# Arduino_DUE_X_V02d-2Layer.net
KiCad netlist of a schematic drawn in Altium Designer
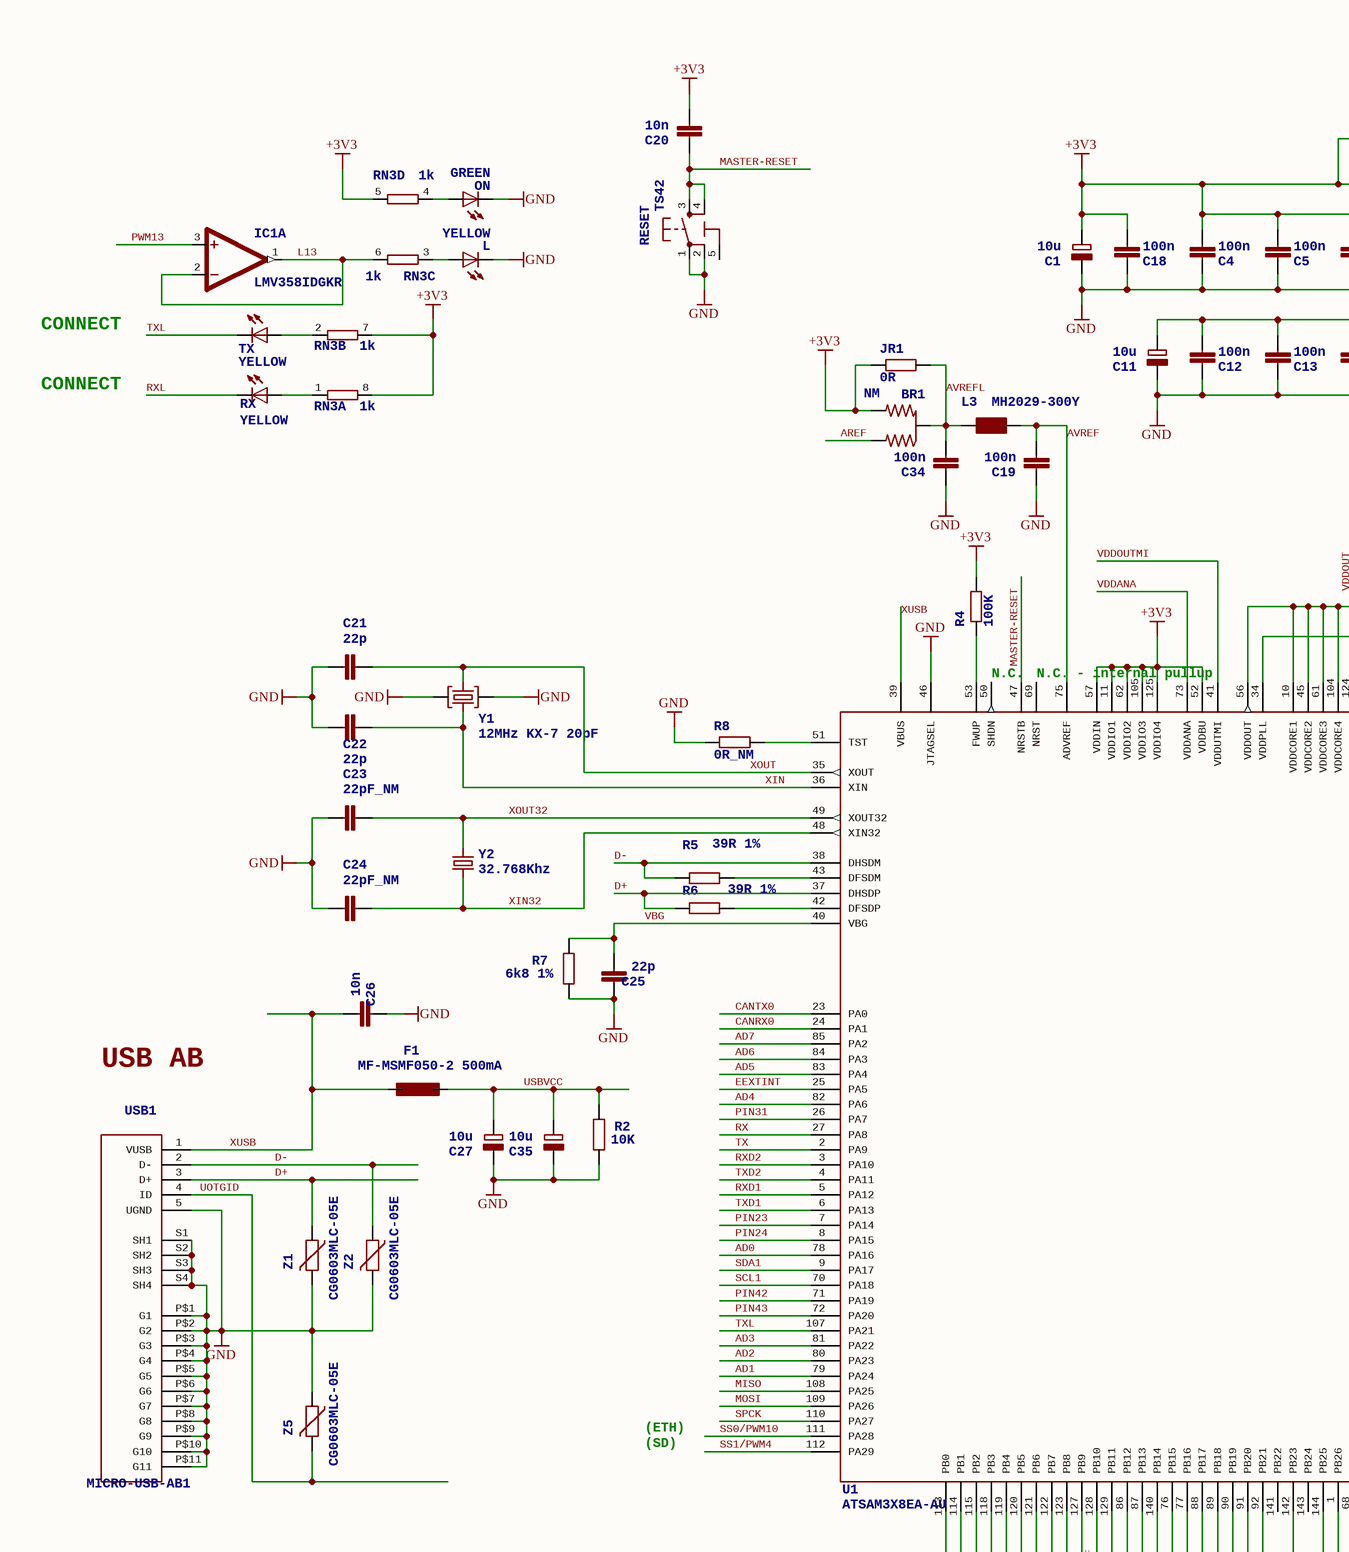
[diagram p0: Arduino_DUE_X_V02d-2Layer.SchDoc, top left]
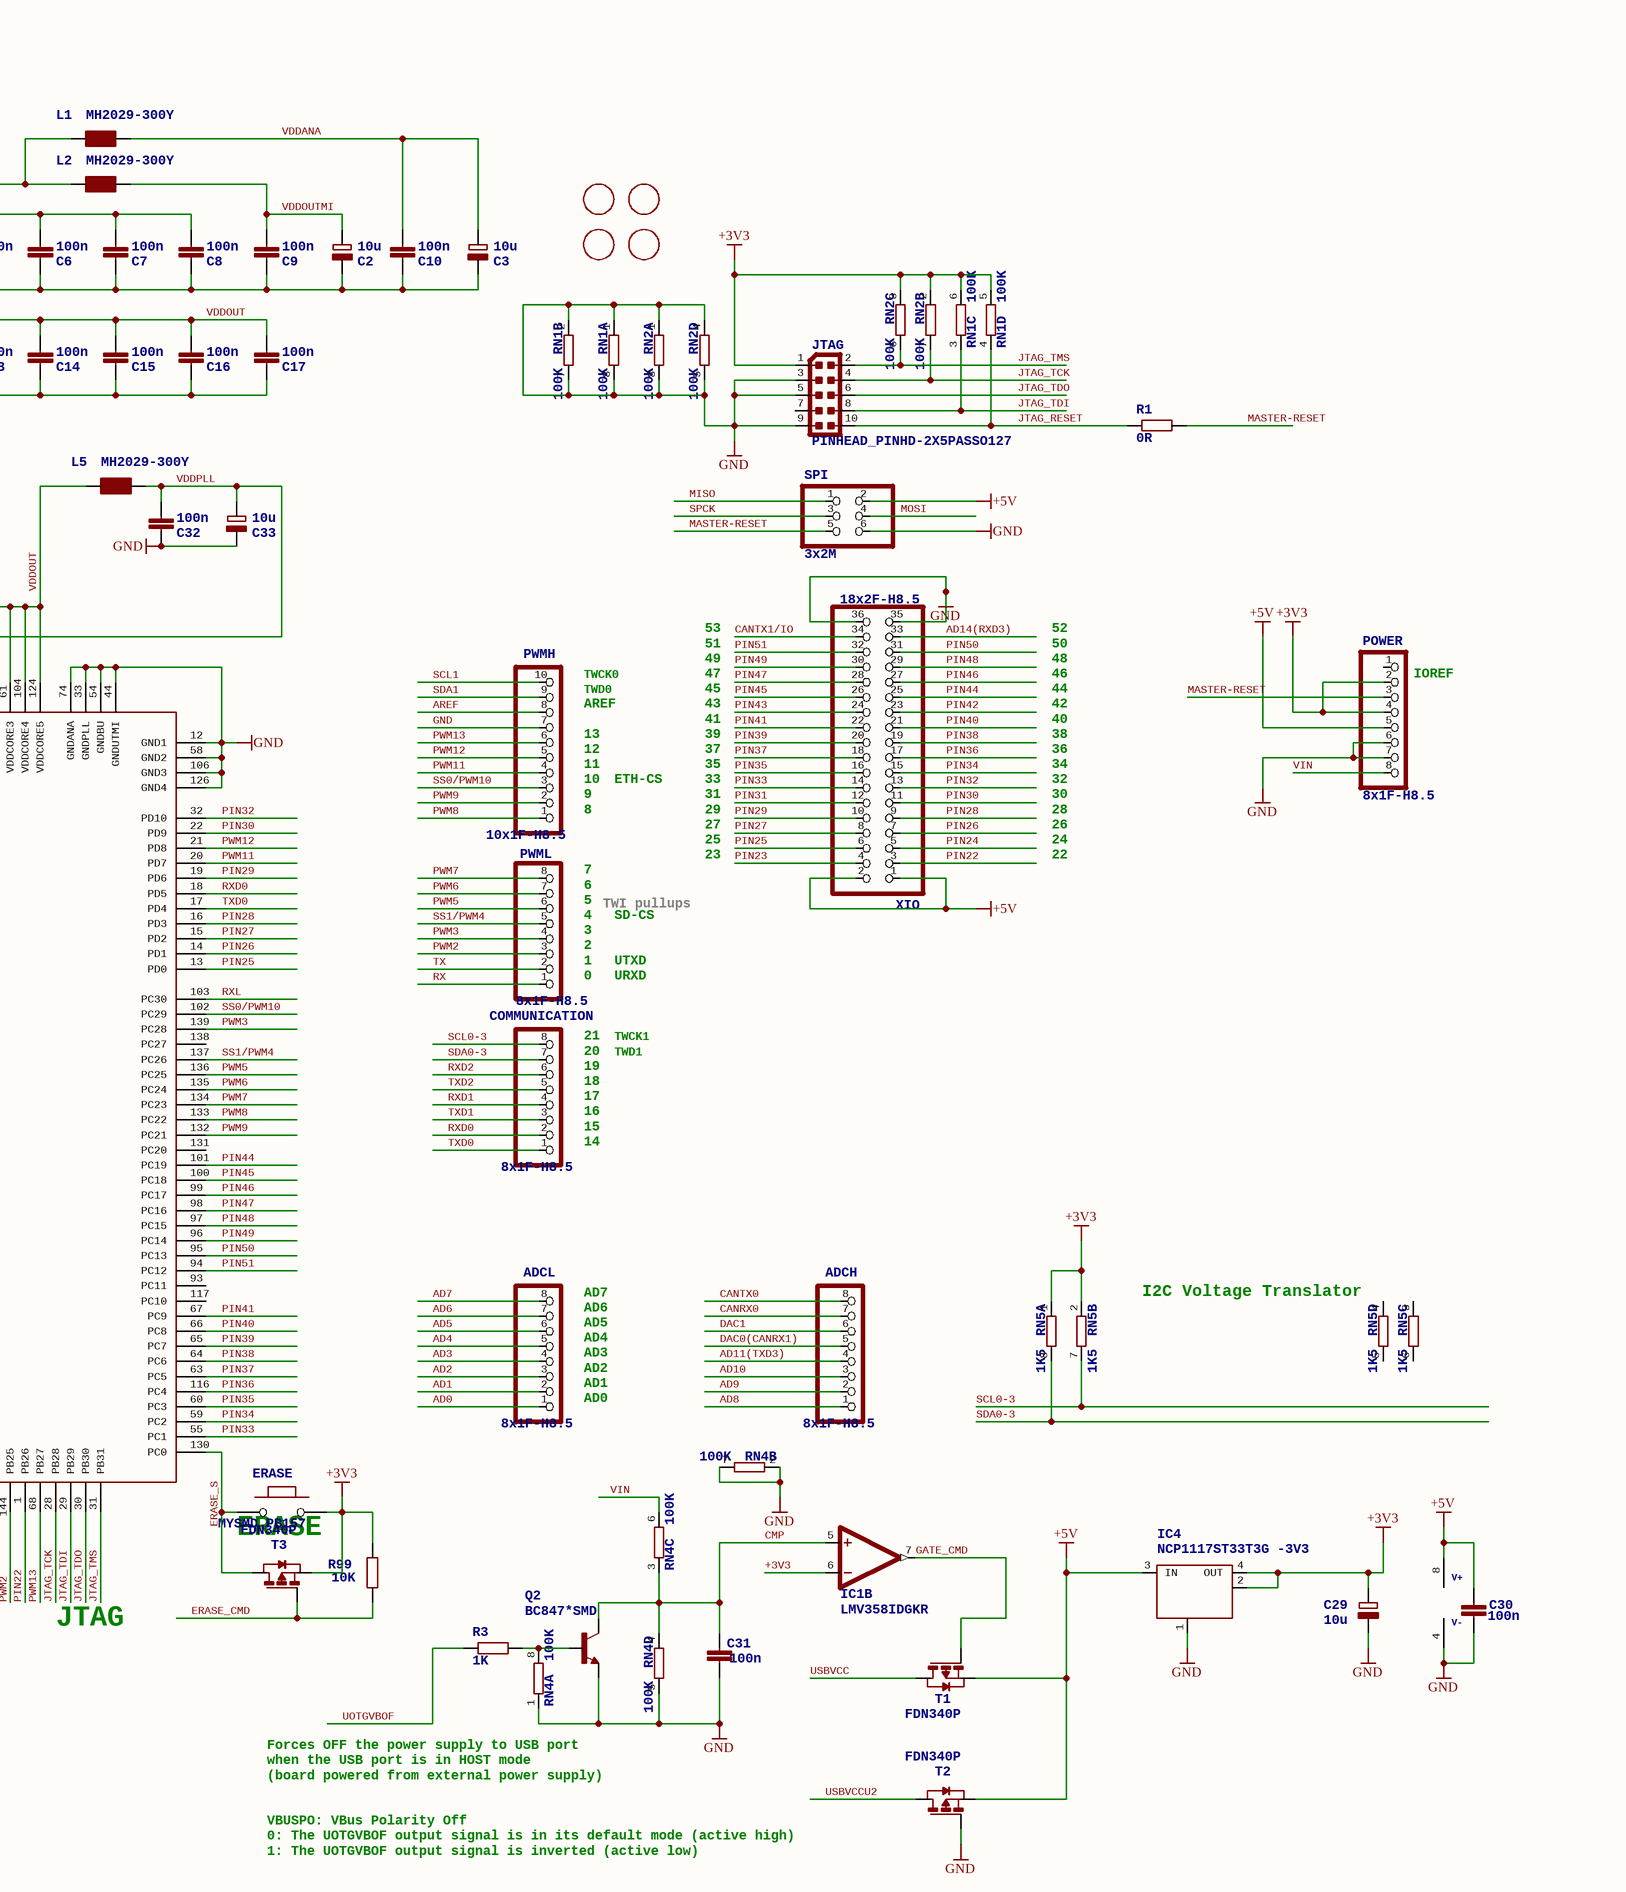
[diagram p1: Arduino_DUE_X_V02d-2Layer.SchDoc, top right]
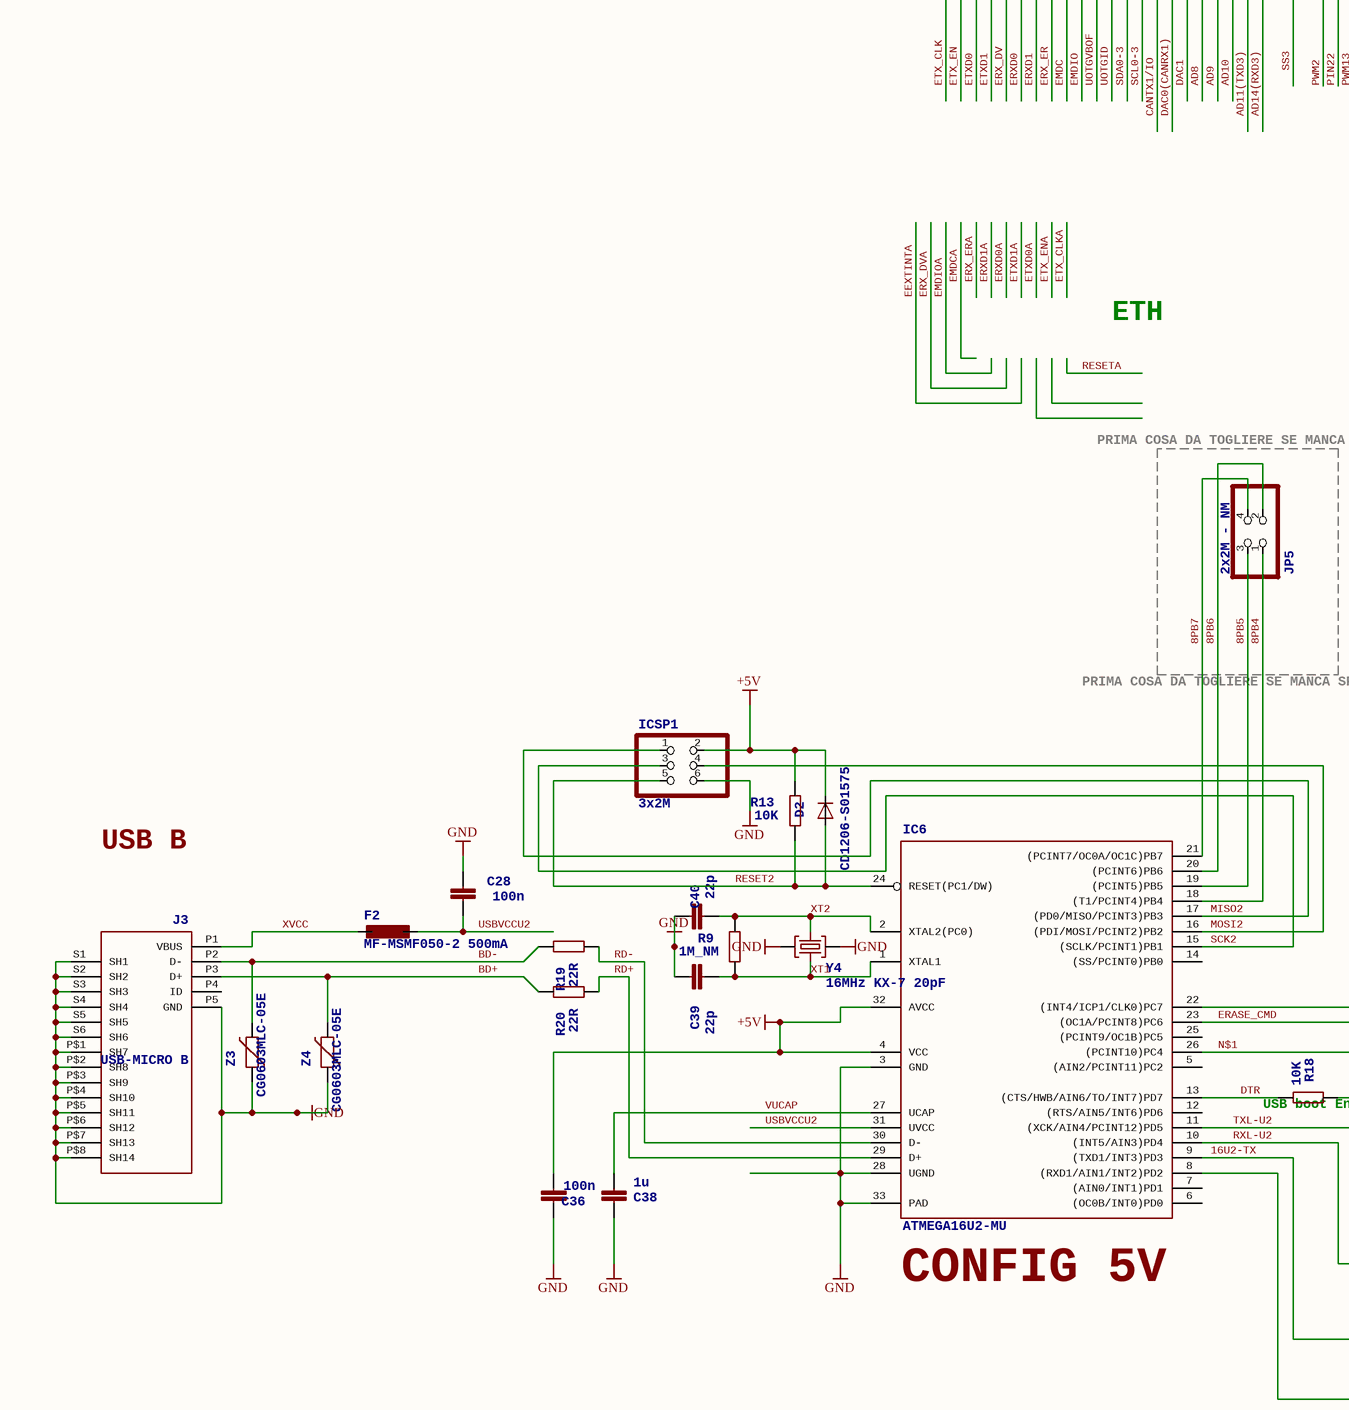
[diagram p2: Arduino_DUE_X_V02d-2Layer.SchDoc, bottom left]
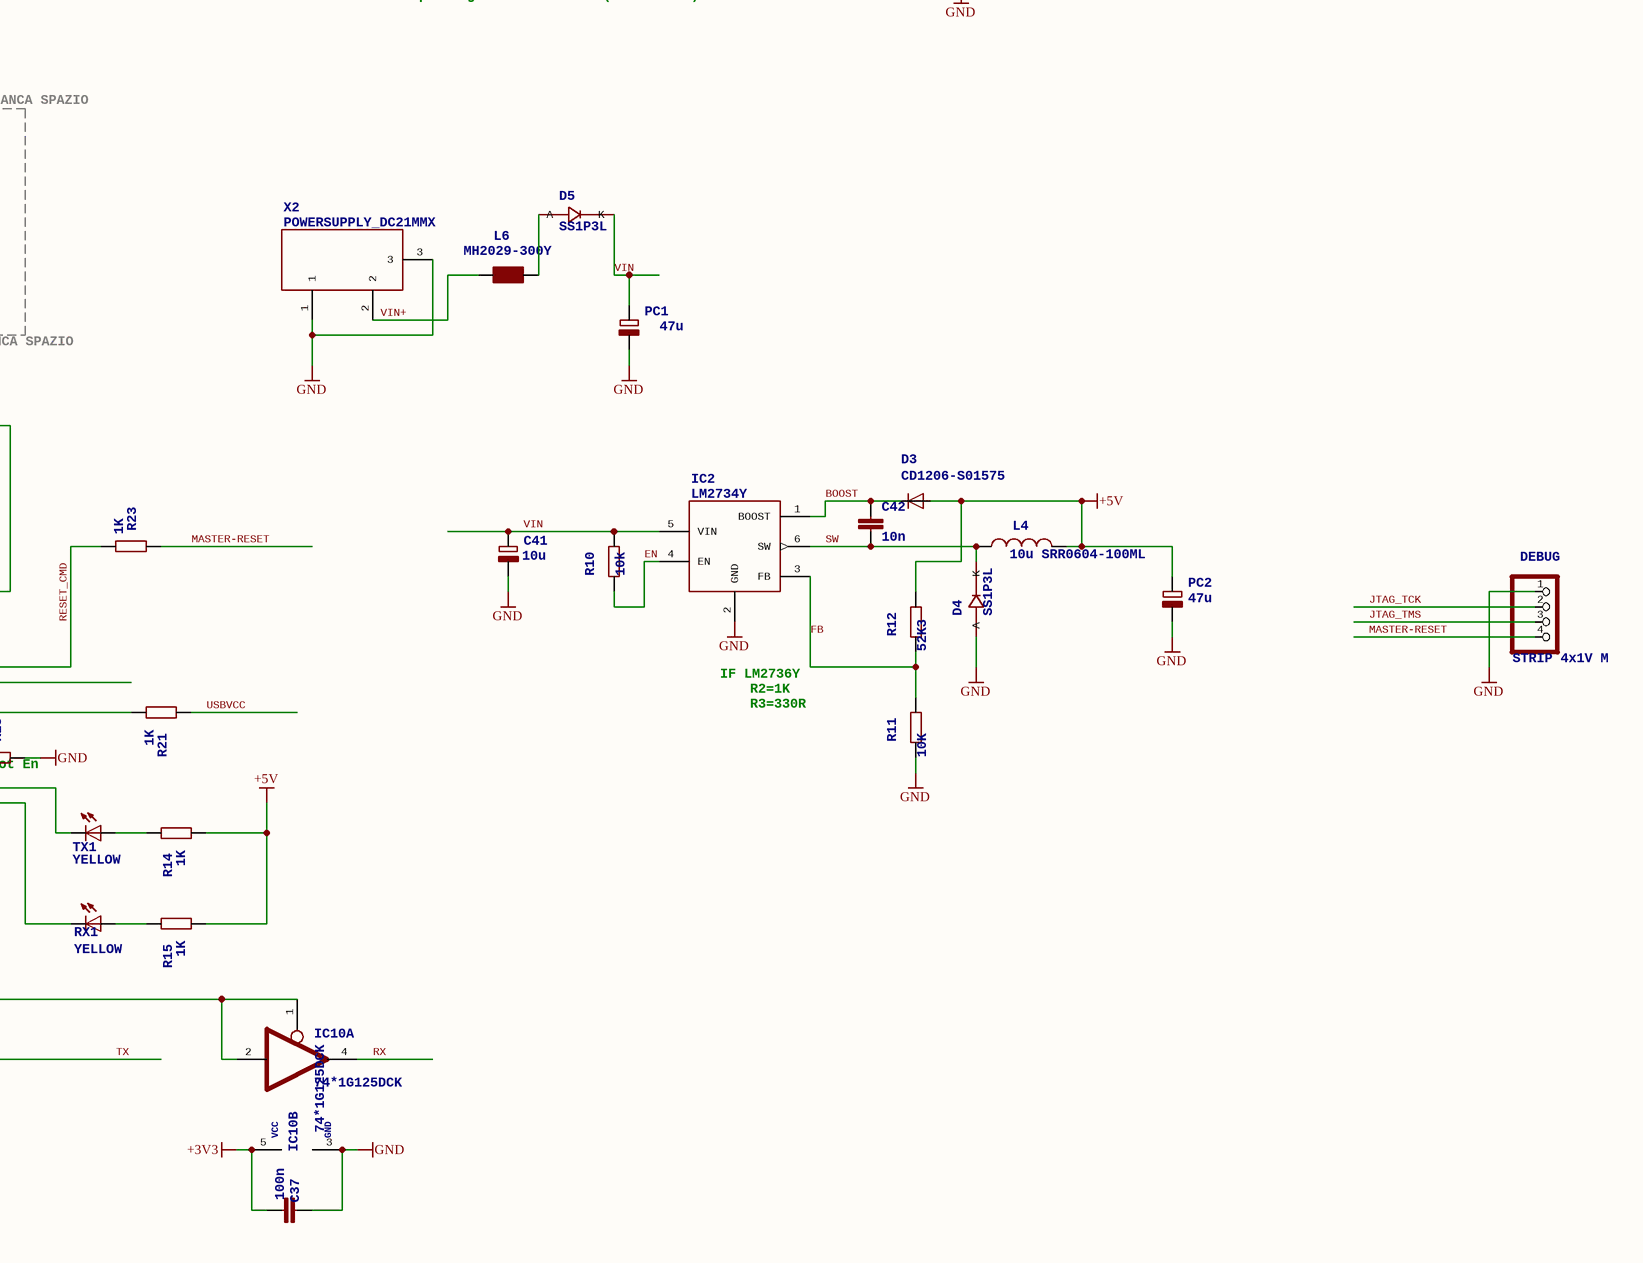
[diagram p3: Arduino_DUE_X_V02d-2Layer.SchDoc, bottom right]

(export (version "E")
  (design (tool "Eeschema 10.0.6"))
  (components
    (comp (ref "ADCH")
      (value "8x1F-H8.5")
      (footprint "1X08")
      (description "<b>PIN HEADER</b>")
      (libsource (lib "SmartPrj") (part "PINHD-1X8"))
    )
    (comp (ref "ADCL")
      (value "8x1F-H8.5")
      (footprint "1X08")
      (description "<b>PIN HEADER</b>")
      (libsource (lib "SmartPrj") (part "PINHD-1X8"))
    )
    (comp (ref "BR1")
      (value "NM")
      (footprint "J0402")
      (description "Three terminal jumper made from two 0402, 0603, 0805, etc.")
      (libsource (lib "bibaja") (part "J0402"))
    )
    (comp (ref "C1")
      (value "10u")
      (footprint "SMC_B")
      (description "<B>POLARIZED CAPACITOR</B>, European symbol")
      (libsource (lib "rcl") (part "CPOL-EUSMCB"))
    )
    (comp (ref "C2")
      (value "10u")
      (footprint "SMC_B")
      (description "<B>POLARIZED CAPACITOR</B>, European symbol")
      (libsource (lib "") (part "CPOL-EUSMCB_1"))
    )
    (comp (ref "C3")
      (value "10u")
      (footprint "SMC_B")
      (description "<B>POLARIZED CAPACITOR</B>, European symbol")
      (libsource (lib "") (part "CPOL-EUSMCB_1"))
    )
    (comp (ref "C4")
      (value "100n")
      (footprint "C0402")
      (description "<B>CAPACITOR</B>, European symbol")
      (libsource (lib "SmartPrj") (part "C-EUC0402"))
    )
    (comp (ref "C5")
      (value "100n")
      (footprint "C0402")
      (description "<B>CAPACITOR</B>, European symbol")
      (libsource (lib "SmartPrj") (part "C-EUC0402"))
    )
    (comp (ref "C6")
      (value "100n")
      (footprint "C0402")
      (description "<B>CAPACITOR</B>, European symbol")
      (libsource (lib "SmartPrj") (part "C-EUC0402"))
    )
    (comp (ref "C7")
      (value "100n")
      (footprint "C0402")
      (description "<B>CAPACITOR</B>, European symbol")
      (libsource (lib "SmartPrj") (part "C-EUC0402"))
    )
    (comp (ref "C8")
      (value "100n")
      (footprint "C0402")
      (description "<B>CAPACITOR</B>, European symbol")
      (libsource (lib "SmartPrj") (part "C-EUC0402"))
    )
    (comp (ref "C9")
      (value "100n")
      (footprint "C0402")
      (description "<B>CAPACITOR</B>, European symbol")
      (libsource (lib "SmartPrj") (part "C-EUC0402"))
    )
    (comp (ref "C10")
      (value "100n")
      (footprint "C0402")
      (description "<B>CAPACITOR</B>, European symbol")
      (libsource (lib "SmartPrj") (part "C-EUC0402"))
    )
    (comp (ref "C11")
      (value "10u")
      (footprint "SMC_B")
      (description "<B>POLARIZED CAPACITOR</B>, European symbol")
      (libsource (lib "rcl") (part "CPOL-EUSMCB"))
    )
    (comp (ref "C12")
      (value "100n")
      (footprint "C0402")
      (description "<B>CAPACITOR</B>, European symbol")
      (libsource (lib "SmartPrj") (part "C-EUC0402"))
    )
    (comp (ref "C13")
      (value "100n")
      (footprint "C0402")
      (description "<B>CAPACITOR</B>, European symbol")
      (libsource (lib "SmartPrj") (part "C-EUC0402"))
    )
    (comp (ref "C14")
      (value "100n")
      (footprint "C0402")
      (description "<B>CAPACITOR</B>, European symbol")
      (libsource (lib "SmartPrj") (part "C-EUC0402"))
    )
    (comp (ref "C15")
      (value "100n")
      (footprint "C0402")
      (description "<B>CAPACITOR</B>, European symbol")
      (libsource (lib "SmartPrj") (part "C-EUC0402"))
    )
    (comp (ref "C16")
      (value "100n")
      (footprint "C0402")
      (description "<B>CAPACITOR</B>, European symbol")
      (libsource (lib "SmartPrj") (part "C-EUC0402"))
    )
    (comp (ref "C17")
      (value "100n")
      (footprint "C0402")
      (description "<B>CAPACITOR</B>, European symbol")
      (libsource (lib "SmartPrj") (part "C-EUC0402"))
    )
    (comp (ref "C18")
      (value "100n")
      (footprint "C0402")
      (description "<B>CAPACITOR</B>, European symbol")
      (libsource (lib "SmartPrj") (part "C-EUC0402"))
    )
    (comp (ref "C19")
      (value "100n")
      (footprint "C0402")
      (description "<B>CAPACITOR</B>, European symbol")
      (libsource (lib "") (part "C-EUC0402_1"))
    )
    (comp (ref "C20")
      (value "10n")
      (footprint "C0402")
      (description "<B>CAPACITOR</B>, European symbol")
      (libsource (lib "") (part "C-EUC0402_1"))
    )
    (comp (ref "C21")
      (value "22p")
      (footprint "C0402")
      (description "<B>CAPACITOR</B>, European symbol")
      (libsource (lib "") (part "C-EUC0402_2"))
    )
    (comp (ref "C22")
      (value "22p")
      (footprint "C0402")
      (description "<B>CAPACITOR</B>, European symbol")
      (libsource (lib "") (part "C-EUC0402_2"))
    )
    (comp (ref "C23")
      (value "22pF_NM")
      (footprint "C0402")
      (description "<B>CAPACITOR</B>, European symbol")
      (libsource (lib "") (part "C-EUC0402_2"))
    )
    (comp (ref "C24")
      (value "22pF_NM")
      (footprint "C0402")
      (description "<B>CAPACITOR</B>, European symbol")
      (libsource (lib "") (part "C-EUC0402_2"))
    )
    (comp (ref "C25")
      (value "22p")
      (footprint "C0402")
      (description "<B>CAPACITOR</B>, European symbol")
      (libsource (lib "") (part "C-EUC0402_2"))
    )
    (comp (ref "C26")
      (value "10n")
      (footprint "C0402")
      (description "<B>CAPACITOR</B>, European symbol")
      (libsource (lib "SmartPrj") (part "C-EUC0402"))
    )
    (comp (ref "C27")
      (value "10u")
      (footprint "SMC_B")
      (description "<B>POLARIZED CAPACITOR</B>, European symbol")
      (libsource (lib "rcl") (part "CPOL-EUSMCB"))
    )
    (comp (ref "C28")
      (value "100n")
      (footprint "C0402")
      (description "<B>CAPACITOR</B>, European symbol")
      (libsource (lib "") (part "C-EUC0402_1"))
    )
    (comp (ref "C29")
      (value "10u")
      (footprint "SMC_B")
      (description "<B>POLARIZED CAPACITOR</B>, European symbol")
      (libsource (lib "rcl") (part "CPOL-EUSMCB"))
    )
    (comp (ref "C30")
      (value "100n")
      (footprint "C0402")
      (description "<B>CAPACITOR</B>, European symbol")
      (libsource (lib "SmartPrj") (part "C-EUC0402"))
    )
    (comp (ref "C31")
      (value "100n")
      (footprint "C0402")
      (description "<B>CAPACITOR</B>, European symbol")
      (libsource (lib "SmartPrj") (part "C-EUC0402"))
    )
    (comp (ref "C32")
      (value "100n")
      (footprint "C0402")
      (description "<B>CAPACITOR</B>, European symbol")
      (libsource (lib "SmartPrj") (part "C-EUC0402"))
    )
    (comp (ref "C33")
      (value "10u")
      (footprint "SMC_B")
      (description "<B>POLARIZED CAPACITOR</B>, European symbol")
      (libsource (lib "") (part "CPOL-EUSMCB_1"))
    )
    (comp (ref "C34")
      (value "100n")
      (footprint "C0402")
      (description "<B>CAPACITOR</B>, European symbol")
      (libsource (lib "") (part "C-EUC0402_1"))
    )
    (comp (ref "C35")
      (value "10u")
      (footprint "SMC_B")
      (description "<B>POLARIZED CAPACITOR</B>, European symbol")
      (libsource (lib "rcl") (part "CPOL-EUSMCB"))
    )
    (comp (ref "C36")
      (value "100n")
      (footprint "C0402")
      (description "<B>CAPACITOR</B>, European symbol")
      (libsource (lib "") (part "C-EUC0402_2"))
    )
    (comp (ref "C37")
      (value "100n")
      (footprint "C0402")
      (description "<B>CAPACITOR</B>, European symbol")
      (libsource (lib "SmartPrj") (part "C-EUC0402"))
    )
    (comp (ref "C38")
      (value "1u")
      (footprint "C0402")
      (description "<B>CAPACITOR</B>, European symbol")
      (libsource (lib "") (part "C-EUC0402_2"))
    )
    (comp (ref "C39")
      (value "22p")
      (footprint "C0402")
      (description "<B>CAPACITOR</B>, European symbol")
      (libsource (lib "") (part "C-EUC0402_2"))
    )
    (comp (ref "C40")
      (value "22p")
      (footprint "C0402")
      (description "<B>CAPACITOR</B>, European symbol")
      (libsource (lib "") (part "C-EUC0402_2"))
    )
    (comp (ref "C41")
      (value "10u")
      (footprint "SMC_B")
      (description "<B>POLARIZED CAPACITOR</B>, European symbol")
      (libsource (lib "rcl") (part "CPOL-EUSMCB"))
    )
    (comp (ref "C42")
      (value "10n")
      (footprint "C0603-ROUND")
      (description "<B>CAPACITOR</B>, European symbol")
      (libsource (lib "SmartPrj") (part "C-EUC0603"))
    )
    (comp (ref "COMMUNICATION")
      (value "8x1F-H8.5")
      (footprint "1X08")
      (description "<b>PIN HEADER</b>")
      (libsource (lib "SmartPrj") (part "PINHD-1X8"))
    )
    (comp (ref "D2")
      (value "CD1206-S01575")
      (footprint "MINIMELF")
      (description "<b>DIODE</b>")
      (libsource (lib "diode") (part "DIODE-MINIMELF"))
    )
    (comp (ref "D3")
      (value "CD1206-S01575")
      (footprint "MINIMELF")
      (description "<b>DIODE</b>")
      (libsource (lib "diode") (part "DIODE-MINIMELF"))
    )
    (comp (ref "D4") (value "SS1P3L") (footprint "DO220AAL") (libsource (lib "SmartPrj") (part "SS1P3L")))
    (comp (ref "D5") (value "SS1P3L") (footprint "DO220AAL") (libsource (lib "SmartPrj") (part "SS1P3L")))
    (comp (ref "DEBUG")
      (value "STRIP 4x1V M")
      (footprint "1X04")
      (description "<b>PIN HEADER</b>")
      (libsource (lib "pinhead") (part "PINHD-1X4"))
    )
    (comp (ref "ERASE")
      (value "MYSMD_PB157")
      (footprint "SMD_157SW")
      (libsource (lib "SmartPrj") (part "MYSMD_PB157"))
    )
    (comp (ref "F1")
      (value "MF-MSMF050-2 500mA")
      (footprint "L1812")
      (description "<B>INDUCTOR</B>, European symbol")
      (libsource (lib "rcl") (part "L-EUL1812"))
    )
    (comp (ref "F2")
      (value "MF-MSMF050-2 500mA")
      (footprint "L1812")
      (description "<B>INDUCTOR</B>, European symbol")
      (libsource (lib "rcl") (part "L-EUL1812"))
    )
    (comp (ref "FID1")
      (value "FIDUCIALMOUNT")
      (footprint "FIDUCIA-MOUNT")
      (libsource (lib "SmartPrj") (part "FIDUCIALMOUNT"))
    )
    (comp (ref "FID2")
      (value "FIDUCIALMOUNT")
      (footprint "FIDUCIA-MOUNT")
      (libsource (lib "SmartPrj") (part "FIDUCIALMOUNT"))
    )
    (comp (ref "FID3")
      (value "FIDUCIALMOUNT")
      (footprint "FIDUCIA-MOUNT")
      (libsource (lib "SmartPrj") (part "FIDUCIALMOUNT"))
    )
    (comp (ref "FID4")
      (value "FIDUCIALMOUNT")
      (footprint "FIDUCIA-MOUNT")
      (libsource (lib "SmartPrj") (part "FIDUCIALMOUNT"))
    )
    (comp (ref "IC1")
      (value "LMV358IDGKR")
      (footprint "MSOP08")
      (fields (field (name "V+") "V+") (field (name "V-") "V-"))
      (libsource (lib "linear") (part "LMV358?*MM"))
    )
    (comp (ref "IC2") (value "LM2734Y") (footprint "SOT23-6") (libsource (lib "SmartPrj") (part "LM2736Y")))
    (comp (ref "IC4")
      (value "NCP1117ST33T3G -3V3")
      (footprint "SOT223")
      (libsource (lib "linear") (part "MC33269ST*"))
    )
    (comp (ref "IC6")
      (value "ATMEGA16U2-MU")
      (footprint "MLF32")
      (libsource (lib "SmartPrj") (part "ATMEGA16U2-MU"))
    )
    (comp (ref "IC10")
      (value "74*1G125DCK")
      (footprint "SC70-5")
      (description "Single Bus <b>Buffer </b>Gate with 3-State Output")
      (fields (field (name "GND") "GND") (field (name "VCC") "VCC"))
      (libsource (lib "74xx-little-us") (part "74*1G125DCK"))
    )
    (comp (ref "ICSP1")
      (value "3x2M")
      (footprint "2X03")
      (description "<b>PIN HEADER</b>")
      (libsource (lib "SmartPrj") (part "PINHD-2X3"))
    )
    (comp (ref "J3")
      (value "USB-MICRO B")
      (footprint "CON2_USB_MICRO_B_AT")
      (libsource (lib "SmartPrj") (part "MYCON2_USB-MINI-B"))
    )
    (comp (ref "JP5")
      (value "2x2M - NM")
      (footprint "2X02")
      (description "<b>PIN HEADER</b>")
      (libsource (lib "SmartPrj") (part "PINHD-2X2"))
    )
    (comp (ref "JR1")
      (value "0R")
      (footprint "R0402")
      (description "<B>RESISTOR</B>, European symbol")
      (libsource (lib "SmartPrj") (part "R-EU_R0402"))
    )
    (comp (ref "JTAG")
      (value "PINHEAD_PINHD-2X5PASSO127")
      (footprint "PINHEAD_2X05_127")
      (description "<b>PIN HEADER</b>")
      (libsource (lib "Arduino_Wifi_shield_v018_tG") (part "PINHEAD_PINHD-2X5PASSO127"))
    )
    (comp (ref "L")
      (value "YELLOW")
      (footprint "CHIP-LED0805")
      (libsource (lib "led") (part "LEDCHIP-LED0805"))
    )
    (comp (ref "L1")
      (value "MH2029-300Y")
      (footprint "0805")
      (libsource (lib "wuerth-elektronik") (part "WE-CBF_0805"))
    )
    (comp (ref "L2")
      (value "MH2029-300Y")
      (footprint "0805")
      (libsource (lib "wuerth-elektronik") (part "WE-CBF_0805"))
    )
    (comp (ref "L3")
      (value "MH2029-300Y")
      (footprint "0805")
      (libsource (lib "wuerth-elektronik") (part "WE-CBF_0805"))
    )
    (comp (ref "L4")
      (value "10u SRR0604-100ML")
      (footprint "SRR0604")
      (description "<B>INDUCTOR</B>, American symbol")
      (libsource (lib "SmartPrj") (part "L-USSRR0604"))
    )
    (comp (ref "L5")
      (value "MH2029-300Y")
      (footprint "0805")
      (libsource (lib "wuerth-elektronik") (part "WE-CBF_0805"))
    )
    (comp (ref "L6") (value "MH2029-300Y") (footprint "0805") (libsource (lib "") (part "WE-CBF_0805_1")))
    (comp (ref "ON")
      (value "GREEN")
      (footprint "CHIP-LED0805")
      (libsource (lib "led") (part "LEDCHIP-LED0805"))
    )
    (comp (ref "PC1")
      (value "47u")
      (footprint "PANASONIC_D")
      (description "<B>POLARIZED CAPACITOR</B>, European symbol")
      (libsource (lib "rcl") (part "CPOL-EUD"))
    )
    (comp (ref "PC2")
      (value "47u")
      (footprint "PANASONIC_D")
      (description "<B>POLARIZED CAPACITOR</B>, European symbol")
      (libsource (lib "rcl") (part "CPOL-EUD"))
    )
    (comp (ref "POWER")
      (value "8x1F-H8.5")
      (footprint "1X08")
      (description "<b>PIN HEADER</b>")
      (libsource (lib "SmartPrj") (part "PINHD-1X8"))
    )
    (comp (ref "PWMH")
      (value "10x1F-H8.5")
      (footprint "1X10")
      (description "<b>PIN HEADER</b>")
      (libsource (lib "SmartPrj") (part "PINHD-1X10"))
    )
    (comp (ref "PWML")
      (value "8x1F-H8.5")
      (footprint "1X08")
      (description "<b>PIN HEADER</b>")
      (libsource (lib "SmartPrj") (part "PINHD-1X8"))
    )
    (comp (ref "Q2")
      (value "BC847*SMD")
      (footprint "SOT23")
      (description "NPN Transistor")
      (libsource (lib "transistor-npn") (part "BC847*SMD"))
    )
    (comp (ref "R1")
      (value "0R")
      (footprint "R0402")
      (description "<B>RESISTOR</B>, European symbol")
      (libsource (lib "SmartPrj") (part "R-EU_R0402"))
    )
    (comp (ref "R2")
      (value "10K")
      (footprint "R0402")
      (description "<B>RESISTOR</B>, European symbol")
      (libsource (lib "SmartPrj") (part "R-EU_R0402"))
    )
    (comp (ref "R3")
      (value "1K")
      (footprint "R0402")
      (description "<B>RESISTOR</B>, European symbol")
      (libsource (lib "SmartPrj") (part "R-EU_R0402"))
    )
    (comp (ref "R4")
      (value "100K")
      (footprint "R0402")
      (description "<B>RESISTOR</B>, European symbol")
      (libsource (lib "SmartPrj") (part "R-EU_R0402"))
    )
    (comp (ref "R5")
      (value "39R 1%")
      (footprint "R0402")
      (description "<B>RESISTOR</B>, European symbol")
      (libsource (lib "SmartPrj") (part "R-EU_R0402"))
    )
    (comp (ref "R6")
      (value "39R 1%")
      (footprint "R0402")
      (description "<B>RESISTOR</B>, European symbol")
      (libsource (lib "SmartPrj") (part "R-EU_R0402"))
    )
    (comp (ref "R7")
      (value "6k8 1%")
      (footprint "R0603-ROUND")
      (description "<B>RESISTOR</B>, European symbol")
      (libsource (lib "SmartPrj") (part "R-EU_R0603"))
    )
    (comp (ref "R8")
      (value "0R_NM")
      (footprint "R0402")
      (description "<B>RESISTOR</B>, European symbol")
      (libsource (lib "SmartPrj") (part "R-EU_R0402"))
    )
    (comp (ref "R9")
      (value "1M_NM")
      (footprint "R0402")
      (description "<B>RESISTOR</B>, European symbol")
      (libsource (lib "SmartPrj") (part "R-EU_R0402"))
    )
    (comp (ref "R10")
      (value "10k")
      (footprint "R0402")
      (description "<B>RESISTOR</B>, European symbol")
      (libsource (lib "SmartPrj") (part "R-EU_R0402"))
    )
    (comp (ref "R11")
      (value "10K")
      (footprint "R0603-ROUND")
      (description "<B>RESISTOR</B>, European symbol")
      (libsource (lib "SmartPrj") (part "R-EU_0603-RND"))
    )
    (comp (ref "R12")
      (value "52K3")
      (footprint "R0603-ROUND")
      (description "<B>RESISTOR</B>, European symbol")
      (libsource (lib "SmartPrj") (part "R-EU_0603-RND"))
    )
    (comp (ref "R13")
      (value "10K")
      (footprint "R0402")
      (description "<B>RESISTOR</B>, European symbol")
      (libsource (lib "SmartPrj") (part "R-EU_R0402"))
    )
    (comp (ref "R14")
      (value "1K")
      (footprint "R0402")
      (description "<B>RESISTOR</B>, European symbol")
      (libsource (lib "SmartPrj") (part "R-EU_R0402"))
    )
    (comp (ref "R15")
      (value "1K")
      (footprint "R0402")
      (description "<B>RESISTOR</B>, European symbol")
      (libsource (lib "SmartPrj") (part "R-EU_R0402"))
    )
    (comp (ref "R18")
      (value "10K")
      (footprint "R0402")
      (description "<B>RESISTOR</B>, European symbol")
      (libsource (lib "SmartPrj") (part "R-EU_R0402"))
    )
    (comp (ref "R19")
      (value "22R")
      (footprint "R0402")
      (description "<B>RESISTOR</B>, European symbol")
      (libsource (lib "SmartPrj") (part "R-EU_R0402"))
    )
    (comp (ref "R20")
      (value "22R")
      (footprint "R0402")
      (description "<B>RESISTOR</B>, European symbol")
      (libsource (lib "SmartPrj") (part "R-EU_R0402"))
    )
    (comp (ref "R21")
      (value "1K")
      (footprint "R0402")
      (description "<B>RESISTOR</B>, European symbol")
      (libsource (lib "SmartPrj") (part "R-EU_R0402"))
    )
    (comp (ref "R23")
      (value "1K")
      (footprint "R0402")
      (description "<B>RESISTOR</B>, European symbol")
      (libsource (lib "SmartPrj") (part "R-EU_R0402"))
    )
    (comp (ref "R99")
      (value "10K")
      (footprint "R0402")
      (description "<B>RESISTOR</B>, European symbol")
      (libsource (lib "SmartPrj") (part "R-EU_R0402"))
    )
    (comp (ref "RESET")
      (value "TS42")
      (footprint "TS42")
      (description "TS42\n\nDongnan Electronics\n\nTact switch\n\nVDC 12V - 50mA")
      (libsource (lib "SmartPrj") (part "TS42"))
    )
    (comp (ref "RN1")
      (value "100K")
      (footprint "CAT16")
      (description "<b>Array Chip Resistor</b><p>\nSource: RS Component / Phycomp")
      (libsource (lib "resistor-dil") (part "4R-NCAT16"))
    )
    (comp (ref "RN2")
      (value "100K")
      (footprint "CAT16")
      (description "<b>Array Chip Resistor</b><p>\nSource: RS Component / Phycomp")
      (libsource (lib "resistor-dil") (part "4R-NCAT16"))
    )
    (comp (ref "RN3")
      (value "1k")
      (footprint "CAY16")
      (description "<b>Array Chip Resistor</b><p>\nSource: RS Component / Phycomp")
      (libsource (lib "resistor-dil") (part "4R-NCAY16"))
    )
    (comp (ref "RN4")
      (value "100K")
      (footprint "CAT16")
      (description "<b>Array Chip Resistor</b><p>\nSource: RS Component / Phycomp")
      (libsource (lib "resistor-dil") (part "4R-NCAT16"))
    )
    (comp (ref "RN5")
      (value "1K5")
      (footprint "CAT16")
      (description "<b>Array Chip Resistor</b><p>\nSource: RS Component / Phycomp")
      (libsource (lib "resistor-dil") (part "4R-NCAT16"))
    )
    (comp (ref "RX")
      (value "YELLOW")
      (footprint "CHIP-LED0805")
      (libsource (lib "led") (part "LEDCHIP-LED0805"))
    )
    (comp (ref "RX1")
      (value "YELLOW")
      (footprint "CHIP-LED0805")
      (libsource (lib "led") (part "LEDCHIP-LED0805"))
    )
    (comp (ref "SPI")
      (value "3x2M")
      (footprint "2X03")
      (description "<b>PIN HEADER</b>")
      (libsource (lib "SmartPrj") (part "PINHD-2X3"))
    )
    (comp (ref "T1")
      (value "FDN340P")
      (footprint "SOT-23")
      (description "<b>MOS FET</b>")
      (libsource (lib "") (part "PMOSSOT23_1"))
    )
    (comp (ref "T2")
      (value "FDN340P")
      (footprint "SOT-23")
      (description "<b>MOS FET</b>")
      (libsource (lib "zetex") (part "PMOSSOT23"))
    )
    (comp (ref "T3")
      (value "FDN340P")
      (footprint "SOT-23")
      (description "<b>MOS FET</b>")
      (libsource (lib "zetex") (part "PMOSSOT23"))
    )
    (comp (ref "TX")
      (value "YELLOW")
      (footprint "CHIP-LED0805")
      (libsource (lib "led") (part "LEDCHIP-LED0805"))
    )
    (comp (ref "TX1")
      (value "YELLOW")
      (footprint "CHIP-LED0805")
      (libsource (lib "led") (part "LEDCHIP-LED0805"))
    )
    (comp (ref "U1")
      (value "ATSAM3X8EA-AU")
      (footprint "LQFP144")
      (libsource (lib "SmartPrj") (part "ATSAM3X/AAU"))
    )
    (comp (ref "USB1")
      (value "MICRO-USB-AB1")
      (footprint "MCR-AB1-S-RA-SMT")
      (description "<B>Micro_USB ADAM-TECH</B> MCR-AB1-S-RA-SMT")
      (libsource (lib "SmartPrj") (part "MICRO_USB"))
    )
    (comp (ref "X2")
      (value "POWERSUPPLY_DC21MMX")
      (footprint "POWERSUPPLY_DC-21MM")
      (libsource (lib "SmartPrj") (part "POWERSUPPLY_DC21MMX"))
    )
    (comp (ref "XIO")
      (value "18x2F-H8.5")
      (footprint "2X18")
      (description "<b>PIN HEADER</b>")
      (libsource (lib "SmartPrj") (part "PINHD-2X18"))
    )
    (comp (ref "Y1")
      (value "12MHz KX-7 20pF")
      (footprint "CRYSTAL-3.2-2.5")
      (libsource (lib "SmartPrj") (part "CRYSTAL-3.2-2.5"))
    )
    (comp (ref "Y2")
      (value "32.768Khz")
      (footprint "RESONATOR_EPSON_FC_145")
      (libsource (lib "Arduino_Wifi_shield_v018_tG") (part "RESONATOR_EPSON_FC_145"))
    )
    (comp (ref "Y4")
      (value "16MHz KX-7 20pF")
      (footprint "CRYSTAL-3.2-2.5")
      (libsource (lib "SmartPrj") (part "CRYSTAL-3.2-2.5"))
    )
    (comp (ref "Z1")
      (value "CG0603MLC-05E")
      (footprint "CT/CN0603")
      (description "<b>VARISTOR</b>")
      (libsource (lib "varistor") (part "VARISTORCN0603"))
    )
    (comp (ref "Z2")
      (value "CG0603MLC-05E")
      (footprint "CT/CN0603")
      (description "<b>VARISTOR</b>")
      (libsource (lib "varistor") (part "VARISTORCN0603"))
    )
    (comp (ref "Z3")
      (value "CG0603MLC-05E")
      (footprint "CT/CN0603")
      (description "<b>VARISTOR</b>")
      (libsource (lib "varistor") (part "VARISTORCN0603"))
    )
    (comp (ref "Z4")
      (value "CG0603MLC-05E")
      (footprint "CT/CN0603")
      (description "<b>VARISTOR</b>")
      (libsource (lib "varistor") (part "VARISTORCN0603"))
    )
    (comp (ref "Z5")
      (value "CG0603MLC-05E")
      (footprint "CT/CN0603")
      (description "<b>VARISTOR</b>")
      (libsource (lib "varistor") (part "VARISTORCN0603"))
    )
  )
  (nets
    (net (code "1") (name "+3V3") (class "Default")
      (node (ref "BR1") (pin "3") (pinfunction "2_3") (pintype "passive"))
      (node (ref "C1") (pin "+") (pinfunction "+_+") (pintype "passive"))
      (node (ref "C18") (pin "2") (pinfunction "2_2") (pintype "passive"))
      (node (ref "C20") (pin "2") (pinfunction "2_2") (pintype "passive"))
      (node (ref "C29") (pin "+") (pinfunction "+_+") (pintype "passive"))
      (node (ref "C37") (pin "1") (pinfunction "1_1") (pintype "passive"))
      (node (ref "C4") (pin "2") (pinfunction "2_2") (pintype "passive"))
      (node (ref "C5") (pin "2") (pinfunction "2_2") (pintype "passive"))
      (node (ref "C6") (pin "2") (pinfunction "2_2") (pintype "passive"))
      (node (ref "C7") (pin "2") (pinfunction "2_2") (pintype "passive"))
      (node (ref "C8") (pin "2") (pinfunction "2_2") (pintype "passive"))
      (node (ref "ERASE") (pin "1") (pinfunction "1_1") (pintype "passive"))
      (node (ref "IC1") (pin "6") (pinfunction "-IN_6") (pintype "passive"))
      (node (ref "IC10") (pin "5") (pinfunction "VCC_5") (pintype "power_in"))
      (node (ref "IC4") (pin "2") (pinfunction "OUT_2") (pintype "passive"))
      (node (ref "IC4") (pin "4") (pinfunction "OUT_4") (pintype "passive"))
      (node (ref "JR1") (pin "1") (pinfunction "1_1") (pintype "passive"))
      (node (ref "JTAG") (pin "1") (pinfunction "1_1") (pintype "passive"))
      (node (ref "L1") (pin "1") (pinfunction "1_1") (pintype "passive"))
      (node (ref "L2") (pin "1") (pinfunction "1_1") (pintype "passive"))
      (node (ref "POWER") (pin "2") (pinfunction "2_2") (pintype "passive"))
      (node (ref "POWER") (pin "4") (pinfunction "4_4") (pintype "passive"))
      (node (ref "R4") (pin "2") (pinfunction "2_2") (pintype "passive"))
      (node (ref "R99") (pin "2") (pinfunction "2_2") (pintype "passive"))
      (node (ref "RN1") (pin "5") (pinfunction "2_5") (pintype "passive"))
      (node (ref "RN1") (pin "6") (pinfunction "2_6") (pintype "passive"))
      (node (ref "RN2") (pin "2") (pinfunction "1_2") (pintype "passive"))
      (node (ref "RN2") (pin "3") (pinfunction "1_3") (pintype "passive"))
      (node (ref "RN3") (pin "5") (pinfunction "2_5") (pintype "passive"))
      (node (ref "RN3") (pin "7") (pinfunction "2_7") (pintype "passive"))
      (node (ref "RN3") (pin "8") (pinfunction "2_8") (pintype "passive"))
      (node (ref "RN5") (pin "1") (pinfunction "1_1") (pintype "passive"))
      (node (ref "RN5") (pin "2") (pinfunction "1_2") (pintype "passive"))
      (node (ref "T3") (pin "2") (pinfunction "S_2") (pintype "passive"))
      (node (ref "U1") (pin "105") (pinfunction "VDDIO3_105") (pintype "power_in"))
      (node (ref "U1") (pin "11") (pinfunction "VDDIO1_11") (pintype "power_in"))
      (node (ref "U1") (pin "125") (pinfunction "VDDIO4_125") (pintype "power_in"))
      (node (ref "U1") (pin "52") (pinfunction "VDDBU_52") (pintype "power_in"))
      (node (ref "U1") (pin "57") (pinfunction "VDDIN_57") (pintype "power_in"))
      (node (ref "U1") (pin "62") (pinfunction "VDDIO2_62") (pintype "power_in"))
    )
    (net (code "2") (name "+5V") (class "Default")
      (node (ref "C30") (pin "2") (pinfunction "2_2") (pintype "passive"))
      (node (ref "C36") (pin "1") (pinfunction "1_1") (pintype "passive"))
      (node (ref "D2") (pin "C") (pinfunction "C_C") (pintype "passive"))
      (node (ref "D3") (pin "A") (pinfunction "A_A") (pintype "passive"))
      (node (ref "IC1") (pin "8") (pinfunction "V+_8") (pintype "power_in"))
      (node (ref "IC4") (pin "3") (pinfunction "IN_3") (pintype "passive"))
      (node (ref "IC6") (pin "32") (pinfunction "AVCC_32") (pintype "power_in"))
      (node (ref "IC6") (pin "4") (pinfunction "VCC_4") (pintype "power_in"))
      (node (ref "ICSP1") (pin "2") (pinfunction "2_2") (pintype "passive"))
      (node (ref "L4") (pin "P$2") (pinfunction "2_P$2") (pintype "passive"))
      (node (ref "PC2") (pin "+") (pinfunction "+_+") (pintype "passive"))
      (node (ref "POWER") (pin "5") (pinfunction "5_5") (pintype "passive"))
      (node (ref "R12") (pin "1") (pinfunction "1_1") (pintype "passive"))
      (node (ref "R13") (pin "2") (pinfunction "2_2") (pintype "passive"))
      (node (ref "R14") (pin "1") (pinfunction "1_1") (pintype "passive"))
      (node (ref "R15") (pin "1") (pinfunction "1_1") (pintype "passive"))
      (node (ref "SPI") (pin "2") (pinfunction "2_2") (pintype "passive"))
      (node (ref "T1") (pin "2") (pinfunction "S_2") (pintype "passive"))
      (node (ref "T2") (pin "2") (pinfunction "S_2") (pintype "passive"))
      (node (ref "XIO") (pin "1") (pinfunction "1_1") (pintype "passive"))
      (node (ref "XIO") (pin "2") (pinfunction "2_2") (pintype "passive"))
    )
    (net (code "3") (name "/8PB4") (class "Default")
      (node (ref "IC6") (pin "18") (pinfunction "(T1/PCINT4)PB4_18") (pintype "passive"))
      (node (ref "JP5") (pin "1") (pinfunction "1_1") (pintype "passive"))
    )
    (net (code "4") (name "/8PB5") (class "Default")
      (node (ref "IC6") (pin "19") (pinfunction "(PCINT5)PB5_19") (pintype "passive"))
      (node (ref "JP5") (pin "3") (pinfunction "3_3") (pintype "passive"))
    )
    (net (code "5") (name "/8PB6") (class "Default")
      (node (ref "IC6") (pin "20") (pinfunction "(PCINT6)PB6_20") (pintype "passive"))
      (node (ref "JP5") (pin "2") (pinfunction "2_2") (pintype "passive"))
    )
    (net (code "6") (name "/8PB7") (class "Default")
      (node (ref "IC6") (pin "21") (pinfunction "(PCINT7/OC0A/OC1C)PB7_21") (pintype "passive"))
      (node (ref "JP5") (pin "4") (pinfunction "4_4") (pintype "passive"))
    )
    (net (code "7") (name "/16U2-TX") (class "Default")
      (node (ref "IC10") (pin "1") (pinfunction "OE_1") (pintype "passive"))
      (node (ref "IC10") (pin "2") (pinfunction "I_2") (pintype "passive"))
      (node (ref "IC6") (pin "9") (pinfunction "(TXD1/INT3)PD3_9") (pintype "passive"))
    )
    (net (code "8") (name "/AD0") (class "Default")
      (node (ref "ADCL") (pin "1") (pinfunction "1_1") (pintype "passive"))
      (node (ref "U1") (pin "78") (pinfunction "PA16_78") (pintype "passive"))
    )
    (net (code "9") (name "/AD1") (class "Default")
      (node (ref "ADCL") (pin "2") (pinfunction "2_2") (pintype "passive"))
      (node (ref "U1") (pin "79") (pinfunction "PA24_79") (pintype "passive"))
    )
    (net (code "10") (name "/AD2") (class "Default")
      (node (ref "ADCL") (pin "3") (pinfunction "3_3") (pintype "passive"))
      (node (ref "U1") (pin "80") (pinfunction "PA23_80") (pintype "passive"))
    )
    (net (code "11") (name "/AD3") (class "Default")
      (node (ref "ADCL") (pin "4") (pinfunction "4_4") (pintype "passive"))
      (node (ref "U1") (pin "81") (pinfunction "PA22_81") (pintype "passive"))
    )
    (net (code "12") (name "/AD4") (class "Default")
      (node (ref "ADCL") (pin "5") (pinfunction "5_5") (pintype "passive"))
      (node (ref "U1") (pin "82") (pinfunction "PA6_82") (pintype "passive"))
    )
    (net (code "13") (name "/AD5") (class "Default")
      (node (ref "ADCL") (pin "6") (pinfunction "6_6") (pintype "passive"))
      (node (ref "U1") (pin "83") (pinfunction "PA4_83") (pintype "passive"))
    )
    (net (code "14") (name "/AD6") (class "Default")
      (node (ref "ADCL") (pin "7") (pinfunction "7_7") (pintype "passive"))
      (node (ref "U1") (pin "84") (pinfunction "PA3_84") (pintype "passive"))
    )
    (net (code "15") (name "/AD7") (class "Default")
      (node (ref "ADCL") (pin "8") (pinfunction "8_8") (pintype "passive"))
      (node (ref "U1") (pin "85") (pinfunction "PA2_85") (pintype "passive"))
    )
    (net (code "16") (name "/AD8") (class "Default")
      (node (ref "ADCH") (pin "1") (pinfunction "1_1") (pintype "passive"))
      (node (ref "U1") (pin "88") (pinfunction "PB17_88") (pintype "passive"))
    )
    (net (code "17") (name "/AD9") (class "Default")
      (node (ref "ADCH") (pin "2") (pinfunction "2_2") (pintype "passive"))
      (node (ref "U1") (pin "89") (pinfunction "PB18_89") (pintype "passive"))
    )
    (net (code "18") (name "/AD10") (class "Default")
      (node (ref "ADCH") (pin "3") (pinfunction "3_3") (pintype "passive"))
      (node (ref "U1") (pin "90") (pinfunction "PB19_90") (pintype "passive"))
    )
    (net (code "19") (name "/AD11(TXD3)") (class "Default")
      (node (ref "ADCH") (pin "4") (pinfunction "4_4") (pintype "passive"))
      (node (ref "U1") (pin "91") (pinfunction "PB20_91") (pintype "passive"))
    )
    (net (code "20") (name "/AD14(RXD3)") (class "Default")
      (node (ref "U1") (pin "92") (pinfunction "PB21_92") (pintype "passive"))
      (node (ref "XIO") (pin "33") (pinfunction "33_33") (pintype "passive"))
    )
    (net (code "21") (name "/AREF") (class "Default")
      (node (ref "BR1") (pin "1") (pinfunction "1_1") (pintype "passive"))
      (node (ref "PWMH") (pin "8") (pinfunction "8_8") (pintype "passive"))
    )
    (net (code "22") (name "/AVREF") (class "Default")
      (node (ref "C19") (pin "2") (pinfunction "2_2") (pintype "passive"))
      (node (ref "L3") (pin "2") (pinfunction "2_2") (pintype "passive"))
      (node (ref "U1") (pin "75") (pinfunction "ADVREF_75") (pintype "power_in"))
    )
    (net (code "23") (name "/AVREFL") (class "Default")
      (node (ref "BR1") (pin "2") (pinfunction "C_2") (pintype "passive"))
      (node (ref "C34") (pin "2") (pinfunction "2_2") (pintype "passive"))
      (node (ref "JR1") (pin "2") (pinfunction "2_2") (pintype "passive"))
      (node (ref "L3") (pin "1") (pinfunction "1_1") (pintype "passive"))
    )
    (net (code "24") (name "/BD+") (class "Default")
      (node (ref "J3") (pin "P3") (pinfunction "D+_P3") (pintype "passive"))
      (node (ref "R20") (pin "2") (pinfunction "2_2") (pintype "passive"))
      (node (ref "Z4") (pin "2") (pinfunction "2_2") (pintype "passive"))
    )
    (net (code "25") (name "/BD-") (class "Default")
      (node (ref "J3") (pin "P2") (pinfunction "D-_P2") (pintype "passive"))
      (node (ref "R19") (pin "2") (pinfunction "2_2") (pintype "passive"))
      (node (ref "Z3") (pin "2") (pinfunction "2_2") (pintype "passive"))
    )
    (net (code "26") (name "/BOOST") (class "Default")
      (node (ref "C42") (pin "1") (pinfunction "1_1") (pintype "passive"))
      (node (ref "D3") (pin "C") (pinfunction "C_C") (pintype "passive"))
      (node (ref "IC2") (pin "1") (pinfunction "BOOST_1") (pintype "passive"))
    )
    (net (code "27") (name "/CANRX0") (class "Default")
      (node (ref "ADCH") (pin "7") (pinfunction "7_7") (pintype "passive"))
      (node (ref "U1") (pin "24") (pinfunction "PA1_24") (pintype "passive"))
    )
    (net (code "28") (name "/CANTX0") (class "Default")
      (node (ref "ADCH") (pin "8") (pinfunction "8_8") (pintype "passive"))
      (node (ref "U1") (pin "23") (pinfunction "PA0_23") (pintype "passive"))
    )
    (net (code "29") (name "/CANTX1{slash}IO") (class "Default")
      (node (ref "U1") (pin "140") (pinfunction "PB14_140") (pintype "passive"))
      (node (ref "XIO") (pin "34") (pinfunction "34_34") (pintype "passive"))
    )
    (net (code "30") (name "/CMP") (class "Default")
      (node (ref "C31") (pin "2") (pinfunction "2_2") (pintype "passive"))
      (node (ref "IC1") (pin "5") (pinfunction "+IN_5") (pintype "passive"))
      (node (ref "Q2") (pin "3") (pinfunction "C_3") (pintype "passive"))
      (node (ref "RN4") (pin "3") (pinfunction "1_3") (pintype "passive"))
      (node (ref "RN4") (pin "4") (pinfunction "1_4") (pintype "passive"))
    )
    (net (code "31") (name "/D+") (class "Default")
      (node (ref "R6") (pin "1") (pinfunction "1_1") (pintype "passive"))
      (node (ref "U1") (pin "37") (pinfunction "DHSDP_37") (pintype "passive"))
      (node (ref "USB1") (pin "3") (pinfunction "D+_3") (pintype "passive"))
      (node (ref "Z1") (pin "1") (pinfunction "1_1") (pintype "passive"))
    )
    (net (code "32") (name "/D-") (class "Default")
      (node (ref "R5") (pin "1") (pinfunction "1_1") (pintype "passive"))
      (node (ref "U1") (pin "38") (pinfunction "DHSDM_38") (pintype "passive"))
      (node (ref "USB1") (pin "2") (pinfunction "D-_2") (pintype "passive"))
      (node (ref "Z2") (pin "1") (pinfunction "1_1") (pintype "passive"))
    )
    (net (code "33") (name "/DAC0(CANRX1)") (class "Default")
      (node (ref "ADCH") (pin "5") (pinfunction "5_5") (pintype "passive"))
      (node (ref "U1") (pin "76") (pinfunction "PB15_76") (pintype "passive"))
    )
    (net (code "34") (name "/DAC1") (class "Default")
      (node (ref "ADCH") (pin "6") (pinfunction "6_6") (pintype "passive"))
      (node (ref "U1") (pin "77") (pinfunction "PB16_77") (pintype "passive"))
    )
    (net (code "35") (name "/DTR") (class "Default")
      (node (ref "IC6") (pin "13") (pinfunction "(CTS/HWB/AIN6/TO/INT7)PD7_13") (pintype "passive"))
      (node (ref "R18") (pin "1") (pinfunction "1_1") (pintype "passive"))
    )
    (net (code "36") (name "/EEXTINT") (class "Default")
      (node (ref "U1") (pin "25") (pinfunction "PA5_25") (pintype "passive"))
    )
    (net (code "38") (name "/EMDC") (class "Default")
      (node (ref "U1") (pin "123") (pinfunction "PB8_123") (pintype "passive"))
    )
    (net (code "40") (name "/EMDIO") (class "Default")
      (node (ref "U1") (pin "127") (pinfunction "PB9_127") (pintype "passive"))
    )
    (net (code "42") (name "/EN") (class "Default")
      (node (ref "IC2") (pin "4") (pinfunction "EN_4") (pintype "passive"))
      (node (ref "R10") (pin "2") (pinfunction "2_2") (pintype "passive"))
    )
    (net (code "43") (name "/ERASE_CMD") (class "Default")
      (node (ref "IC6") (pin "23") (pinfunction "(OC1A/PCINT8)PC6_23") (pintype "passive"))
      (node (ref "R99") (pin "1") (pinfunction "1_1") (pintype "passive"))
      (node (ref "T3") (pin "3") (pinfunction "G_3") (pintype "passive"))
    )
    (net (code "44") (name "/ERASE_S") (class "Default")
      (node (ref "ERASE") (pin "2") (pinfunction "2_2") (pintype "passive"))
      (node (ref "T3") (pin "1") (pinfunction "D_1") (pintype "passive"))
      (node (ref "U1") (pin "130") (pinfunction "PC0_130") (pintype "passive"))
    )
    (net (code "45") (name "/ERXD0") (class "Default")
      (node (ref "U1") (pin "120") (pinfunction "PB5_120") (pintype "passive"))
    )
    (net (code "47") (name "/ERXD1") (class "Default")
      (node (ref "U1") (pin "121") (pinfunction "PB6_121") (pintype "passive"))
    )
    (net (code "49") (name "/ERX_DV") (class "Default")
      (node (ref "U1") (pin "119") (pinfunction "PB4_119") (pintype "passive"))
    )
    (net (code "51") (name "/ERX_ER") (class "Default")
      (node (ref "U1") (pin "122") (pinfunction "PB7_122") (pintype "passive"))
    )
    (net (code "53") (name "/ETXD0") (class "Default")
      (node (ref "U1") (pin "115") (pinfunction "PB2_115") (pintype "passive"))
    )
    (net (code "55") (name "/ETXD1") (class "Default")
      (node (ref "U1") (pin "118") (pinfunction "PB3_118") (pintype "passive"))
    )
    (net (code "57") (name "/ETX_CLK") (class "Default")
      (node (ref "U1") (pin "113") (pinfunction "PB0_113") (pintype "passive"))
    )
    (net (code "59") (name "/ETX_EN") (class "Default")
      (node (ref "U1") (pin "114") (pinfunction "PB1_114") (pintype "passive"))
    )
    (net (code "61") (name "/FB") (class "Default")
      (node (ref "IC2") (pin "3") (pinfunction "FB_3") (pintype "passive"))
      (node (ref "R11") (pin "1") (pinfunction "1_1") (pintype "passive"))
      (node (ref "R12") (pin "2") (pinfunction "2_2") (pintype "passive"))
    )
    (net (code "62") (name "/GATE_CMD") (class "Default")
      (node (ref "IC1") (pin "7") (pinfunction "OUT_7") (pintype "output"))
      (node (ref "T1") (pin "3") (pinfunction "G_3") (pintype "passive"))
    )
    (net (code "63") (name "/JTAG_RESET") (class "Default")
      (node (ref "JTAG") (pin "10") (pinfunction "10_10") (pintype "passive"))
      (node (ref "R1") (pin "1") (pinfunction "1_1") (pintype "passive"))
      (node (ref "RN1") (pin "4") (pinfunction "1_4") (pintype "passive"))
    )
    (net (code "64") (name "/JTAG_TCK") (class "Default")
      (node (ref "DEBUG") (pin "2") (pinfunction "2_2") (pintype "passive"))
      (node (ref "JTAG") (pin "4") (pinfunction "4_4") (pintype "passive"))
      (node (ref "RN2") (pin "7") (pinfunction "2_7") (pintype "passive"))
      (node (ref "U1") (pin "28") (pinfunction "PB28_28") (pintype "passive"))
    )
    (net (code "65") (name "/JTAG_TDI") (class "Default")
      (node (ref "JTAG") (pin "8") (pinfunction "8_8") (pintype "passive"))
      (node (ref "RN1") (pin "3") (pinfunction "1_3") (pintype "passive"))
      (node (ref "U1") (pin "29") (pinfunction "PB29_29") (pintype "passive"))
    )
    (net (code "66") (name "/JTAG_TDO") (class "Default")
      (node (ref "JTAG") (pin "6") (pinfunction "6_6") (pintype "passive"))
      (node (ref "U1") (pin "30") (pinfunction "PB30_30") (pintype "passive"))
    )
    (net (code "67") (name "/JTAG_TMS") (class "Default")
      (node (ref "DEBUG") (pin "3") (pinfunction "3_3") (pintype "passive"))
      (node (ref "JTAG") (pin "2") (pinfunction "2_2") (pintype "passive"))
      (node (ref "RN2") (pin "6") (pinfunction "2_6") (pintype "passive"))
      (node (ref "U1") (pin "31") (pinfunction "PB31_31") (pintype "passive"))
    )
    (net (code "68") (name "/L13") (class "Default")
      (node (ref "IC1") (pin "1") (pinfunction "OUT_1") (pintype "output"))
      (node (ref "IC1") (pin "2") (pinfunction "-IN_2") (pintype "passive"))
      (node (ref "RN3") (pin "6") (pinfunction "2_6") (pintype "passive"))
    )
    (net (code "69") (name "/MASTER-RESET") (class "Default")
      (node (ref "C20") (pin "1") (pinfunction "1_1") (pintype "passive"))
      (node (ref "DEBUG") (pin "4") (pinfunction "4_4") (pintype "passive"))
      (node (ref "POWER") (pin "3") (pinfunction "3_3") (pintype "passive"))
      (node (ref "R1") (pin "2") (pinfunction "2_2") (pintype "passive"))
      (node (ref "R23") (pin "2") (pinfunction "2_2") (pintype "passive"))
      (node (ref "RESET") (pin "3") (pinfunction "3_3") (pintype "passive"))
      (node (ref "RESET") (pin "4") (pinfunction "4_4") (pintype "passive"))
      (node (ref "SPI") (pin "5") (pinfunction "5_5") (pintype "passive"))
      (node (ref "U1") (pin "47") (pinfunction "NRSTB_47") (pintype "passive"))
    )
    (net (code "70") (name "/MISO") (class "Default")
      (node (ref "SPI") (pin "1") (pinfunction "1_1") (pintype "passive"))
      (node (ref "U1") (pin "108") (pinfunction "PA25_108") (pintype "passive"))
    )
    (net (code "71") (name "/MISO2") (class "Default")
      (node (ref "IC6") (pin "17") (pinfunction "(PD0/MISO/PCINT3)PB3_17") (pintype "passive"))
      (node (ref "ICSP1") (pin "1") (pinfunction "1_1") (pintype "passive"))
    )
    (net (code "72") (name "/MOSI") (class "Default")
      (node (ref "SPI") (pin "4") (pinfunction "4_4") (pintype "passive"))
      (node (ref "U1") (pin "109") (pinfunction "PA26_109") (pintype "passive"))
    )
    (net (code "73") (name "/MOSI2") (class "Default")
      (node (ref "IC6") (pin "16") (pinfunction "(PDI/MOSI/PCINT2)PB2_16") (pintype "passive"))
      (node (ref "ICSP1") (pin "4") (pinfunction "4_4") (pintype "passive"))
    )
    (net (code "74") (name "/N$1") (class "Default")
      (node (ref "IC6") (pin "26") (pinfunction "(PCINT10)PC4_26") (pintype "passive"))
      (node (ref "R21") (pin "1") (pinfunction "1_1") (pintype "passive"))
    )
    (net (code "75") (name "/PIN22") (class "Default")
      (node (ref "U1") (pin "1") (pinfunction "PB26_1") (pintype "passive"))
      (node (ref "XIO") (pin "3") (pinfunction "3_3") (pintype "passive"))
    )
    (net (code "76") (name "/PIN23") (class "Default")
      (node (ref "U1") (pin "7") (pinfunction "PA14_7") (pintype "passive"))
      (node (ref "XIO") (pin "4") (pinfunction "4_4") (pintype "passive"))
    )
    (net (code "77") (name "/PIN24") (class "Default")
      (node (ref "U1") (pin "8") (pinfunction "PA15_8") (pintype "passive"))
      (node (ref "XIO") (pin "5") (pinfunction "5_5") (pintype "passive"))
    )
    (net (code "78") (name "/PIN25") (class "Default")
      (node (ref "U1") (pin "13") (pinfunction "PD0_13") (pintype "passive"))
      (node (ref "XIO") (pin "6") (pinfunction "6_6") (pintype "passive"))
    )
    (net (code "79") (name "/PIN26") (class "Default")
      (node (ref "U1") (pin "14") (pinfunction "PD1_14") (pintype "passive"))
      (node (ref "XIO") (pin "7") (pinfunction "7_7") (pintype "passive"))
    )
    (net (code "80") (name "/PIN27") (class "Default")
      (node (ref "U1") (pin "15") (pinfunction "PD2_15") (pintype "passive"))
      (node (ref "XIO") (pin "8") (pinfunction "8_8") (pintype "passive"))
    )
    (net (code "81") (name "/PIN28") (class "Default")
      (node (ref "U1") (pin "16") (pinfunction "PD3_16") (pintype "passive"))
      (node (ref "XIO") (pin "9") (pinfunction "9_9") (pintype "passive"))
    )
    (net (code "82") (name "/PIN29") (class "Default")
      (node (ref "U1") (pin "19") (pinfunction "PD6_19") (pintype "passive"))
      (node (ref "XIO") (pin "10") (pinfunction "10_10") (pintype "passive"))
    )
    (net (code "83") (name "/PIN30") (class "Default")
      (node (ref "U1") (pin "22") (pinfunction "PD9_22") (pintype "passive"))
      (node (ref "XIO") (pin "11") (pinfunction "11_11") (pintype "passive"))
    )
    (net (code "84") (name "/PIN31") (class "Default")
      (node (ref "U1") (pin "26") (pinfunction "PA7_26") (pintype "passive"))
      (node (ref "XIO") (pin "12") (pinfunction "12_12") (pintype "passive"))
    )
    (net (code "85") (name "/PIN32") (class "Default")
      (node (ref "U1") (pin "32") (pinfunction "PD10_32") (pintype "passive"))
      (node (ref "XIO") (pin "13") (pinfunction "13_13") (pintype "passive"))
    )
    (net (code "86") (name "/PIN33") (class "Default")
      (node (ref "U1") (pin "55") (pinfunction "PC1_55") (pintype "passive"))
      (node (ref "XIO") (pin "14") (pinfunction "14_14") (pintype "passive"))
    )
    (net (code "87") (name "/PIN34") (class "Default")
      (node (ref "U1") (pin "59") (pinfunction "PC2_59") (pintype "passive"))
      (node (ref "XIO") (pin "15") (pinfunction "15_15") (pintype "passive"))
    )
    (net (code "88") (name "/PIN35") (class "Default")
      (node (ref "U1") (pin "60") (pinfunction "PC3_60") (pintype "passive"))
      (node (ref "XIO") (pin "16") (pinfunction "16_16") (pintype "passive"))
    )
    (net (code "89") (name "/PIN36") (class "Default")
      (node (ref "U1") (pin "116") (pinfunction "PC4_116") (pintype "passive"))
      (node (ref "XIO") (pin "17") (pinfunction "17_17") (pintype "passive"))
    )
    (net (code "90") (name "/PIN37") (class "Default")
      (node (ref "U1") (pin "63") (pinfunction "PC5_63") (pintype "passive"))
      (node (ref "XIO") (pin "18") (pinfunction "18_18") (pintype "passive"))
    )
    (net (code "91") (name "/PIN38") (class "Default")
      (node (ref "U1") (pin "64") (pinfunction "PC6_64") (pintype "passive"))
      (node (ref "XIO") (pin "19") (pinfunction "19_19") (pintype "passive"))
    )
    (net (code "92") (name "/PIN39") (class "Default")
      (node (ref "U1") (pin "65") (pinfunction "PC7_65") (pintype "passive"))
      (node (ref "XIO") (pin "20") (pinfunction "20_20") (pintype "passive"))
    )
    (net (code "93") (name "/PIN40") (class "Default")
      (node (ref "U1") (pin "66") (pinfunction "PC8_66") (pintype "passive"))
      (node (ref "XIO") (pin "21") (pinfunction "21_21") (pintype "passive"))
    )
    (net (code "94") (name "/PIN41") (class "Default")
      (node (ref "U1") (pin "67") (pinfunction "PC9_67") (pintype "passive"))
      (node (ref "XIO") (pin "22") (pinfunction "22_22") (pintype "passive"))
    )
    (net (code "95") (name "/PIN42") (class "Default")
      (node (ref "U1") (pin "71") (pinfunction "PA19_71") (pintype "passive"))
      (node (ref "XIO") (pin "23") (pinfunction "23_23") (pintype "passive"))
    )
    (net (code "96") (name "/PIN43") (class "Default")
      (node (ref "U1") (pin "72") (pinfunction "PA20_72") (pintype "passive"))
      (node (ref "XIO") (pin "24") (pinfunction "24_24") (pintype "passive"))
    )
    (net (code "97") (name "/PIN44") (class "Default")
      (node (ref "U1") (pin "101") (pinfunction "PC19_101") (pintype "passive"))
      (node (ref "XIO") (pin "25") (pinfunction "25_25") (pintype "passive"))
    )
    (net (code "98") (name "/PIN45") (class "Default")
      (node (ref "U1") (pin "100") (pinfunction "PC18_100") (pintype "passive"))
      (node (ref "XIO") (pin "26") (pinfunction "26_26") (pintype "passive"))
    )
    (net (code "99") (name "/PIN46") (class "Default")
      (node (ref "U1") (pin "99") (pinfunction "PC17_99") (pintype "passive"))
      (node (ref "XIO") (pin "27") (pinfunction "27_27") (pintype "passive"))
    )
    (net (code "100") (name "/PIN47") (class "Default")
      (node (ref "U1") (pin "98") (pinfunction "PC16_98") (pintype "passive"))
      (node (ref "XIO") (pin "28") (pinfunction "28_28") (pintype "passive"))
    )
    (net (code "101") (name "/PIN48") (class "Default")
      (node (ref "U1") (pin "97") (pinfunction "PC15_97") (pintype "passive"))
      (node (ref "XIO") (pin "29") (pinfunction "29_29") (pintype "passive"))
    )
    (net (code "102") (name "/PIN49") (class "Default")
      (node (ref "U1") (pin "96") (pinfunction "PC14_96") (pintype "passive"))
      (node (ref "XIO") (pin "30") (pinfunction "30_30") (pintype "passive"))
    )
    (net (code "103") (name "/PIN50") (class "Default")
      (node (ref "U1") (pin "95") (pinfunction "PC13_95") (pintype "passive"))
      (node (ref "XIO") (pin "31") (pinfunction "31_31") (pintype "passive"))
    )
    (net (code "104") (name "/PIN51") (class "Default")
      (node (ref "U1") (pin "94") (pinfunction "PC12_94") (pintype "passive"))
      (node (ref "XIO") (pin "32") (pinfunction "32_32") (pintype "passive"))
    )
    (net (code "105") (name "/PWM2") (class "Default")
      (node (ref "PWML") (pin "3") (pinfunction "3_3") (pintype "passive"))
      (node (ref "U1") (pin "144") (pinfunction "PB25_144") (pintype "passive"))
    )
    (net (code "106") (name "/PWM3") (class "Default")
      (node (ref "PWML") (pin "4") (pinfunction "4_4") (pintype "passive"))
      (node (ref "U1") (pin "139") (pinfunction "PC28_139") (pintype "passive"))
    )
    (net (code "107") (name "/PWM5") (class "Default")
      (node (ref "PWML") (pin "6") (pinfunction "6_6") (pintype "passive"))
      (node (ref "U1") (pin "136") (pinfunction "PC25_136") (pintype "passive"))
    )
    (net (code "108") (name "/PWM6") (class "Default")
      (node (ref "PWML") (pin "7") (pinfunction "7_7") (pintype "passive"))
      (node (ref "U1") (pin "135") (pinfunction "PC24_135") (pintype "passive"))
    )
    (net (code "109") (name "/PWM7") (class "Default")
      (node (ref "PWML") (pin "8") (pinfunction "8_8") (pintype "passive"))
      (node (ref "U1") (pin "134") (pinfunction "PC23_134") (pintype "passive"))
    )
    (net (code "110") (name "/PWM8") (class "Default")
      (node (ref "PWMH") (pin "1") (pinfunction "1_1") (pintype "passive"))
      (node (ref "U1") (pin "133") (pinfunction "PC22_133") (pintype "passive"))
    )
    (net (code "111") (name "/PWM9") (class "Default")
      (node (ref "PWMH") (pin "2") (pinfunction "2_2") (pintype "passive"))
      (node (ref "U1") (pin "132") (pinfunction "PC21_132") (pintype "passive"))
    )
    (net (code "112") (name "/PWM11") (class "Default")
      (node (ref "PWMH") (pin "4") (pinfunction "4_4") (pintype "passive"))
      (node (ref "U1") (pin "20") (pinfunction "PD7_20") (pintype "passive"))
    )
    (net (code "113") (name "/PWM12") (class "Default")
      (node (ref "PWMH") (pin "5") (pinfunction "5_5") (pintype "passive"))
      (node (ref "U1") (pin "21") (pinfunction "PD8_21") (pintype "passive"))
    )
    (net (code "114") (name "/PWM13") (class "Default")
      (node (ref "IC1") (pin "3") (pinfunction "+IN_3") (pintype "passive"))
      (node (ref "PWMH") (pin "6") (pinfunction "6_6") (pintype "passive"))
      (node (ref "U1") (pin "68") (pinfunction "PB27_68") (pintype "passive"))
    )
    (net (code "115") (name "/RD+") (class "Default")
      (node (ref "IC6") (pin "29") (pinfunction "D+_29") (pintype "passive"))
      (node (ref "R20") (pin "1") (pinfunction "1_1") (pintype "passive"))
    )
    (net (code "116") (name "/RD-") (class "Default")
      (node (ref "IC6") (pin "30") (pinfunction "D-_30") (pintype "passive"))
      (node (ref "R19") (pin "1") (pinfunction "1_1") (pintype "passive"))
    )
    (net (code "117") (name "/RESET2") (class "Default")
      (node (ref "D2") (pin "A") (pinfunction "A_A") (pintype "passive"))
      (node (ref "IC6") (pin "24") (pinfunction "RESET(PC1/DW)_24") (pintype "passive"))
      (node (ref "ICSP1") (pin "5") (pinfunction "5_5") (pintype "passive"))
      (node (ref "R13") (pin "1") (pinfunction "1_1") (pintype "passive"))
    )
    (net (code "119") (name "/RESET_CMD") (class "Default")
      (node (ref "IC6") (pin "22") (pinfunction "(INT4/ICP1/CLK0)PC7_22") (pintype "passive"))
      (node (ref "R23") (pin "1") (pinfunction "1_1") (pintype "passive"))
    )
    (net (code "120") (name "/RX") (class "Default")
      (node (ref "IC10") (pin "4") (pinfunction "O_4") (pintype "tri_state"))
      (node (ref "PWML") (pin "1") (pinfunction "1_1") (pintype "passive"))
      (node (ref "U1") (pin "27") (pinfunction "PA8_27") (pintype "passive"))
    )
    (net (code "121") (name "/RXD0") (class "Default")
      (node (ref "COMMUNICATION") (pin "2") (pinfunction "2_2") (pintype "passive"))
      (node (ref "U1") (pin "18") (pinfunction "PD5_18") (pintype "passive"))
    )
    (net (code "122") (name "/RXD1") (class "Default")
      (node (ref "COMMUNICATION") (pin "4") (pinfunction "4_4") (pintype "passive"))
      (node (ref "U1") (pin "5") (pinfunction "PA12_5") (pintype "passive"))
    )
    (net (code "123") (name "/RXD2") (class "Default")
      (node (ref "COMMUNICATION") (pin "6") (pinfunction "6_6") (pintype "passive"))
      (node (ref "U1") (pin "3") (pinfunction "PA10_3") (pintype "passive"))
    )
    (net (code "124") (name "/RXL") (class "Default")
      (node (ref "RX") (pin "C") (pinfunction "C_C") (pintype "passive"))
      (node (ref "U1") (pin "103") (pinfunction "PC30_103") (pintype "passive"))
    )
    (net (code "125") (name "/RXL-U2") (class "Default")
      (node (ref "IC6") (pin "10") (pinfunction "(INT5/AIN3)PD4_10") (pintype "passive"))
      (node (ref "RX1") (pin "C") (pinfunction "C_C") (pintype "passive"))
    )
    (net (code "126") (name "/SCK2") (class "Default")
      (node (ref "IC6") (pin "15") (pinfunction "(SCLK/PCINT1)PB1_15") (pintype "passive"))
      (node (ref "ICSP1") (pin "3") (pinfunction "3_3") (pintype "passive"))
    )
    (net (code "127") (name "/SCL0-3") (class "Default")
      (node (ref "COMMUNICATION") (pin "8") (pinfunction "8_8") (pintype "passive"))
      (node (ref "RN5") (pin "7") (pinfunction "2_7") (pintype "passive"))
      (node (ref "U1") (pin "87") (pinfunction "PB13_87") (pintype "passive"))
    )
    (net (code "128") (name "/SCL1") (class "Default")
      (node (ref "PWMH") (pin "10") (pinfunction "10_10") (pintype "passive"))
      (node (ref "U1") (pin "70") (pinfunction "PA18_70") (pintype "passive"))
    )
    (net (code "129") (name "/SDA0-3") (class "Default")
      (node (ref "COMMUNICATION") (pin "7") (pinfunction "7_7") (pintype "passive"))
      (node (ref "RN5") (pin "8") (pinfunction "2_8") (pintype "passive"))
      (node (ref "U1") (pin "86") (pinfunction "PB12_86") (pintype "passive"))
    )
    (net (code "130") (name "/SDA1") (class "Default")
      (node (ref "PWMH") (pin "9") (pinfunction "9_9") (pintype "passive"))
      (node (ref "U1") (pin "9") (pinfunction "PA17_9") (pintype "passive"))
    )
    (net (code "131") (name "/SPCK") (class "Default")
      (node (ref "SPI") (pin "3") (pinfunction "3_3") (pintype "passive"))
      (node (ref "U1") (pin "110") (pinfunction "PA27_110") (pintype "passive"))
    )
    (net (code "132") (name "/SS0{slash}PWM10") (class "Default")
      (node (ref "PWMH") (pin "3") (pinfunction "3_3") (pintype "passive"))
      (node (ref "U1") (pin "102") (pinfunction "PC29_102") (pintype "passive"))
      (node (ref "U1") (pin "111") (pinfunction "PA28_111") (pintype "passive"))
    )
    (net (code "133") (name "/SS1{slash}PWM4") (class "Default")
      (node (ref "PWML") (pin "5") (pinfunction "5_5") (pintype "passive"))
      (node (ref "U1") (pin "112") (pinfunction "PA29_112") (pintype "passive"))
      (node (ref "U1") (pin "137") (pinfunction "PC26_137") (pintype "passive"))
    )
    (net (code "134") (name "/SS3") (class "Default")
      (node (ref "U1") (pin "142") (pinfunction "PB23_142") (pintype "passive"))
    )
    (net (code "135") (name "/SW") (class "Default")
      (node (ref "C42") (pin "2") (pinfunction "2_2") (pintype "passive"))
      (node (ref "D4") (pin "P$1") (pinfunction "K_P$1") (pintype "passive"))
      (node (ref "IC2") (pin "6") (pinfunction "SW_6") (pintype "output"))
      (node (ref "L4") (pin "P$1") (pinfunction "1_P$1") (pintype "passive"))
    )
    (net (code "136") (name "/TX") (class "Default")
      (node (ref "IC6") (pin "8") (pinfunction "(RXD1/AIN1/INT2)PD2_8") (pintype "passive"))
      (node (ref "PWML") (pin "2") (pinfunction "2_2") (pintype "passive"))
      (node (ref "U1") (pin "2") (pinfunction "PA9_2") (pintype "passive"))
    )
    (net (code "137") (name "/TXD0") (class "Default")
      (node (ref "COMMUNICATION") (pin "1") (pinfunction "1_1") (pintype "passive"))
      (node (ref "U1") (pin "17") (pinfunction "PD4_17") (pintype "passive"))
    )
    (net (code "138") (name "/TXD1") (class "Default")
      (node (ref "COMMUNICATION") (pin "3") (pinfunction "3_3") (pintype "passive"))
      (node (ref "U1") (pin "6") (pinfunction "PA13_6") (pintype "passive"))
    )
    (net (code "139") (name "/TXD2") (class "Default")
      (node (ref "COMMUNICATION") (pin "5") (pinfunction "5_5") (pintype "passive"))
      (node (ref "U1") (pin "4") (pinfunction "PA11_4") (pintype "passive"))
    )
    (net (code "140") (name "/TXL") (class "Default")
      (node (ref "TX") (pin "C") (pinfunction "C_C") (pintype "passive"))
      (node (ref "U1") (pin "107") (pinfunction "PA21_107") (pintype "passive"))
    )
    (net (code "141") (name "/TXL-U2") (class "Default")
      (node (ref "IC6") (pin "11") (pinfunction "(XCK/AIN4/PCINT12)PD5_11") (pintype "passive"))
      (node (ref "TX1") (pin "C") (pinfunction "C_C") (pintype "passive"))
    )
    (net (code "142") (name "/UOTGID") (class "Default")
      (node (ref "U1") (pin "129") (pinfunction "PB11_129") (pintype "passive"))
      (node (ref "USB1") (pin "4") (pinfunction "ID_4") (pintype "passive"))
      (node (ref "Z5") (pin "2") (pinfunction "2_2") (pintype "passive"))
    )
    (net (code "143") (name "/UOTGVBOF") (class "Default")
      (node (ref "R3") (pin "1") (pinfunction "1_1") (pintype "passive"))
      (node (ref "U1") (pin "128") (pinfunction "PB10_128") (pintype "passive"))
    )
    (net (code "144") (name "/USBVCC") (class "Default")
      (node (ref "C27") (pin "+") (pinfunction "+_+") (pintype "passive"))
      (node (ref "C35") (pin "+") (pinfunction "+_+") (pintype "passive"))
      (node (ref "F1") (pin "1") (pinfunction "1_1") (pintype "passive"))
      (node (ref "R2") (pin "2") (pinfunction "2_2") (pintype "passive"))
      (node (ref "R21") (pin "2") (pinfunction "2_2") (pintype "passive"))
      (node (ref "T1") (pin "1") (pinfunction "D_1") (pintype "passive"))
    )
    (net (code "145") (name "/USBVCCU2") (class "Default")
      (node (ref "C28") (pin "1") (pinfunction "1_1") (pintype "passive"))
      (node (ref "F2") (pin "1") (pinfunction "1_1") (pintype "passive"))
      (node (ref "IC6") (pin "31") (pinfunction "UVCC_31") (pintype "power_in"))
      (node (ref "T2") (pin "1") (pinfunction "D_1") (pintype "passive"))
    )
    (net (code "146") (name "/VBG") (class "Default")
      (node (ref "C25") (pin "1") (pinfunction "1_1") (pintype "passive"))
      (node (ref "R7") (pin "2") (pinfunction "2_2") (pintype "passive"))
      (node (ref "U1") (pin "40") (pinfunction "VBG_40") (pintype "passive"))
    )
    (net (code "147") (name "/VDDANA") (class "Default")
      (node (ref "C10") (pin "2") (pinfunction "2_2") (pintype "passive"))
      (node (ref "C3") (pin "+") (pinfunction "+_+") (pintype "passive"))
      (node (ref "L1") (pin "2") (pinfunction "2_2") (pintype "passive"))
      (node (ref "U1") (pin "73") (pinfunction "VDDANA_73") (pintype "power_in"))
    )
    (net (code "148") (name "/VDDOUT") (class "Default")
      (node (ref "C11") (pin "+") (pinfunction "+_+") (pintype "passive"))
      (node (ref "C12") (pin "2") (pinfunction "2_2") (pintype "passive"))
      (node (ref "C13") (pin "2") (pinfunction "2_2") (pintype "passive"))
      (node (ref "C14") (pin "2") (pinfunction "2_2") (pintype "passive"))
      (node (ref "C15") (pin "2") (pinfunction "2_2") (pintype "passive"))
      (node (ref "C16") (pin "2") (pinfunction "2_2") (pintype "passive"))
      (node (ref "C17") (pin "2") (pinfunction "2_2") (pintype "passive"))
      (node (ref "L5") (pin "1") (pinfunction "1_1") (pintype "passive"))
      (node (ref "U1") (pin "10") (pinfunction "VDDCORE1_10") (pintype "passive"))
      (node (ref "U1") (pin "104") (pinfunction "VDDCORE4_104") (pintype "passive"))
      (node (ref "U1") (pin "124") (pinfunction "VDDCORE5_124") (pintype "passive"))
      (node (ref "U1") (pin "45") (pinfunction "VDDCORE2_45") (pintype "passive"))
      (node (ref "U1") (pin "56") (pinfunction "VDDOUT_56") (pintype "output"))
      (node (ref "U1") (pin "61") (pinfunction "VDDCORE3_61") (pintype "passive"))
    )
    (net (code "149") (name "/VDDOUTMI") (class "Default")
      (node (ref "C2") (pin "+") (pinfunction "+_+") (pintype "passive"))
      (node (ref "C9") (pin "2") (pinfunction "2_2") (pintype "passive"))
      (node (ref "L2") (pin "2") (pinfunction "2_2") (pintype "passive"))
      (node (ref "U1") (pin "41") (pinfunction "VDDUTMI_41") (pintype "passive"))
    )
    (net (code "150") (name "/VDDPLL") (class "Default")
      (node (ref "C32") (pin "2") (pinfunction "2_2") (pintype "passive"))
      (node (ref "C33") (pin "+") (pinfunction "+_+") (pintype "passive"))
      (node (ref "L5") (pin "2") (pinfunction "2_2") (pintype "passive"))
      (node (ref "U1") (pin "34") (pinfunction "VDDPLL_34") (pintype "passive"))
    )
    (net (code "151") (name "/VIN") (class "Default")
      (node (ref "C41") (pin "+") (pinfunction "+_+") (pintype "passive"))
      (node (ref "D5") (pin "P$1") (pinfunction "K_P$1") (pintype "passive"))
      (node (ref "IC2") (pin "5") (pinfunction "VIN_5") (pintype "passive"))
      (node (ref "PC1") (pin "+") (pinfunction "+_+") (pintype "passive"))
      (node (ref "POWER") (pin "8") (pinfunction "8_8") (pintype "passive"))
      (node (ref "R10") (pin "1") (pinfunction "1_1") (pintype "passive"))
      (node (ref "RN4") (pin "6") (pinfunction "2_6") (pintype "passive"))
    )
    (net (code "152") (name "/VIN+") (class "Default")
      (node (ref "L6") (pin "2") (pinfunction "2_2") (pintype "passive"))
      (node (ref "X2") (pin "2") (pinfunction "2_2") (pintype "power_in"))
    )
    (net (code "153") (name "/VUCAP") (class "Default")
      (node (ref "C38") (pin "1") (pinfunction "1_1") (pintype "passive"))
      (node (ref "IC6") (pin "27") (pinfunction "UCAP_27") (pintype "passive"))
    )
    (net (code "154") (name "/XIN") (class "Default")
      (node (ref "C22") (pin "1") (pinfunction "1_1") (pintype "passive"))
      (node (ref "U1") (pin "36") (pinfunction "XIN_36") (pintype "passive"))
      (node (ref "Y1") (pin "1") (pinfunction "C1_1") (pintype "passive"))
    )
    (net (code "155") (name "/XIN32") (class "Default")
      (node (ref "C24") (pin "1") (pinfunction "1_1") (pintype "passive"))
      (node (ref "U1") (pin "48") (pinfunction "XIN32_48") (pintype "output"))
      (node (ref "Y2") (pin "P$2") (pinfunction "2_P$2") (pintype "passive"))
    )
    (net (code "156") (name "/XOUT") (class "Default")
      (node (ref "C21") (pin "1") (pinfunction "1_1") (pintype "passive"))
      (node (ref "U1") (pin "35") (pinfunction "XOUT_35") (pintype "output"))
      (node (ref "Y1") (pin "3") (pinfunction "C2_3") (pintype "passive"))
    )
    (net (code "157") (name "/XOUT32") (class "Default")
      (node (ref "C23") (pin "1") (pinfunction "1_1") (pintype "passive"))
      (node (ref "U1") (pin "49") (pinfunction "XOUT32_49") (pintype "output"))
      (node (ref "Y2") (pin "P$1") (pinfunction "1_P$1") (pintype "passive"))
    )
    (net (code "158") (name "/XT1") (class "Default")
      (node (ref "C39") (pin "1") (pinfunction "1_1") (pintype "passive"))
      (node (ref "IC6") (pin "1") (pinfunction "XTAL1_1") (pintype "passive"))
      (node (ref "R9") (pin "1") (pinfunction "1_1") (pintype "passive"))
      (node (ref "Y4") (pin "1") (pinfunction "C1_1") (pintype "passive"))
    )
    (net (code "159") (name "/XT2") (class "Default")
      (node (ref "C40") (pin "1") (pinfunction "1_1") (pintype "passive"))
      (node (ref "IC6") (pin "2") (pinfunction "XTAL2(PC0)_2") (pintype "passive"))
      (node (ref "R9") (pin "2") (pinfunction "2_2") (pintype "passive"))
      (node (ref "Y4") (pin "3") (pinfunction "C2_3") (pintype "passive"))
    )
    (net (code "160") (name "/XUSB") (class "Default")
      (node (ref "C26") (pin "1") (pinfunction "1_1") (pintype "passive"))
      (node (ref "F1") (pin "2") (pinfunction "2_2") (pintype "passive"))
      (node (ref "U1") (pin "39") (pinfunction "VBUS_39") (pintype "power_in"))
      (node (ref "USB1") (pin "1") (pinfunction "VUSB_1") (pintype "power_in"))
    )
    (net (code "161") (name "/XVCC") (class "Default")
      (node (ref "F2") (pin "2") (pinfunction "2_2") (pintype "passive"))
      (node (ref "J3") (pin "P1") (pinfunction "VBUS_P1") (pintype "power_in"))
    )
    (net (code "162") (name "GND") (class "Default")
      (node (ref "C1") (pin "-") (pinfunction "-_-") (pintype "passive"))
      (node (ref "C10") (pin "1") (pinfunction "1_1") (pintype "passive"))
      (node (ref "C11") (pin "-") (pinfunction "-_-") (pintype "passive"))
      (node (ref "C12") (pin "1") (pinfunction "1_1") (pintype "passive"))
      (node (ref "C13") (pin "1") (pinfunction "1_1") (pintype "passive"))
      (node (ref "C14") (pin "1") (pinfunction "1_1") (pintype "passive"))
      (node (ref "C15") (pin "1") (pinfunction "1_1") (pintype "passive"))
      (node (ref "C16") (pin "1") (pinfunction "1_1") (pintype "passive"))
      (node (ref "C17") (pin "1") (pinfunction "1_1") (pintype "passive"))
      (node (ref "C18") (pin "1") (pinfunction "1_1") (pintype "passive"))
      (node (ref "C19") (pin "1") (pinfunction "1_1") (pintype "passive"))
      (node (ref "C2") (pin "-") (pinfunction "-_-") (pintype "passive"))
      (node (ref "C21") (pin "2") (pinfunction "2_2") (pintype "passive"))
      (node (ref "C22") (pin "2") (pinfunction "2_2") (pintype "passive"))
      (node (ref "C23") (pin "2") (pinfunction "2_2") (pintype "passive"))
      (node (ref "C24") (pin "2") (pinfunction "2_2") (pintype "passive"))
      (node (ref "C25") (pin "2") (pinfunction "2_2") (pintype "passive"))
      (node (ref "C26") (pin "2") (pinfunction "2_2") (pintype "passive"))
      (node (ref "C27") (pin "-") (pinfunction "-_-") (pintype "passive"))
      (node (ref "C28") (pin "2") (pinfunction "2_2") (pintype "passive"))
      (node (ref "C29") (pin "-") (pinfunction "-_-") (pintype "passive"))
      (node (ref "C3") (pin "-") (pinfunction "-_-") (pintype "passive"))
      (node (ref "C30") (pin "1") (pinfunction "1_1") (pintype "passive"))
      (node (ref "C31") (pin "1") (pinfunction "1_1") (pintype "passive"))
      (node (ref "C32") (pin "1") (pinfunction "1_1") (pintype "passive"))
      (node (ref "C33") (pin "-") (pinfunction "-_-") (pintype "passive"))
      (node (ref "C34") (pin "1") (pinfunction "1_1") (pintype "passive"))
      (node (ref "C35") (pin "-") (pinfunction "-_-") (pintype "passive"))
      (node (ref "C36") (pin "2") (pinfunction "2_2") (pintype "passive"))
      (node (ref "C37") (pin "2") (pinfunction "2_2") (pintype "passive"))
      (node (ref "C38") (pin "2") (pinfunction "2_2") (pintype "passive"))
      (node (ref "C39") (pin "2") (pinfunction "2_2") (pintype "passive"))
      (node (ref "C4") (pin "1") (pinfunction "1_1") (pintype "passive"))
      (node (ref "C40") (pin "2") (pinfunction "2_2") (pintype "passive"))
      (node (ref "C41") (pin "-") (pinfunction "-_-") (pintype "passive"))
      (node (ref "C5") (pin "1") (pinfunction "1_1") (pintype "passive"))
      (node (ref "C6") (pin "1") (pinfunction "1_1") (pintype "passive"))
      (node (ref "C7") (pin "1") (pinfunction "1_1") (pintype "passive"))
      (node (ref "C8") (pin "1") (pinfunction "1_1") (pintype "passive"))
      (node (ref "C9") (pin "1") (pinfunction "1_1") (pintype "passive"))
      (node (ref "D4") (pin "P$2") (pinfunction "A_P$2") (pintype "passive"))
      (node (ref "DEBUG") (pin "1") (pinfunction "1_1") (pintype "passive"))
      (node (ref "IC1") (pin "4") (pinfunction "V-_4") (pintype "power_in"))
      (node (ref "IC10") (pin "3") (pinfunction "GND_3") (pintype "power_in"))
      (node (ref "IC2") (pin "2") (pinfunction "GND_2") (pintype "power_in"))
      (node (ref "IC4") (pin "1") (pinfunction "GND/ADJ_1") (pintype "passive"))
      (node (ref "IC6") (pin "28") (pinfunction "UGND_28") (pintype "power_in"))
      (node (ref "IC6") (pin "3") (pinfunction "GND_3") (pintype "power_in"))
      (node (ref "IC6") (pin "33") (pinfunction "PAD_33") (pintype "power_in"))
      (node (ref "ICSP1") (pin "6") (pinfunction "6_6") (pintype "passive"))
      (node (ref "J3") (pin "P$1") (pinfunction "SH7_P$1") (pintype "passive"))
      (node (ref "J3") (pin "P$2") (pinfunction "SH8_P$2") (pintype "passive"))
      (node (ref "J3") (pin "P$3") (pinfunction "SH9_P$3") (pintype "passive"))
      (node (ref "J3") (pin "P$4") (pinfunction "SH10_P$4") (pintype "passive"))
      (node (ref "J3") (pin "P$5") (pinfunction "SH11_P$5") (pintype "passive"))
      (node (ref "J3") (pin "P$6") (pinfunction "SH12_P$6") (pintype "passive"))
      (node (ref "J3") (pin "P$7") (pinfunction "SH13_P$7") (pintype "passive"))
      (node (ref "J3") (pin "P$8") (pinfunction "SH14_P$8") (pintype "passive"))
      (node (ref "J3") (pin "P5") (pinfunction "GND_P5") (pintype "passive"))
      (node (ref "J3") (pin "S1") (pinfunction "SH1_S1") (pintype "passive"))
      (node (ref "J3") (pin "S2") (pinfunction "SH2_S2") (pintype "passive"))
      (node (ref "J3") (pin "S3") (pinfunction "SH3_S3") (pintype "passive"))
      (node (ref "J3") (pin "S4") (pinfunction "SH4_S4") (pintype "passive"))
      (node (ref "J3") (pin "S5") (pinfunction "SH5_S5") (pintype "passive"))
      (node (ref "J3") (pin "S6") (pinfunction "SH6_S6") (pintype "passive"))
      (node (ref "JTAG") (pin "3") (pinfunction "3_3") (pintype "passive"))
      (node (ref "JTAG") (pin "5") (pinfunction "5_5") (pintype "passive"))
      (node (ref "JTAG") (pin "9") (pinfunction "9_9") (pintype "passive"))
      (node (ref "L") (pin "C") (pinfunction "C_C") (pintype "passive"))
      (node (ref "ON") (pin "C") (pinfunction "C_C") (pintype "passive"))
      (node (ref "PC1") (pin "-") (pinfunction "-_-") (pintype "passive"))
      (node (ref "PC2") (pin "-") (pinfunction "-_-") (pintype "passive"))
      (node (ref "POWER") (pin "6") (pinfunction "6_6") (pintype "passive"))
      (node (ref "POWER") (pin "7") (pinfunction "7_7") (pintype "passive"))
      (node (ref "PWMH") (pin "7") (pinfunction "7_7") (pintype "passive"))
      (node (ref "Q2") (pin "2") (pinfunction "E_2") (pintype "passive"))
      (node (ref "R11") (pin "2") (pinfunction "2_2") (pintype "passive"))
      (node (ref "R18") (pin "2") (pinfunction "2_2") (pintype "passive"))
      (node (ref "R2") (pin "1") (pinfunction "1_1") (pintype "passive"))
      (node (ref "R7") (pin "1") (pinfunction "1_1") (pintype "passive"))
      (node (ref "R8") (pin "1") (pinfunction "1_1") (pintype "passive"))
      (node (ref "RESET") (pin "1") (pinfunction "1_1") (pintype "passive"))
      (node (ref "RESET") (pin "2") (pinfunction "2_2") (pintype "passive"))
      (node (ref "RN1") (pin "1") (pinfunction "1_1") (pintype "passive"))
      (node (ref "RN1") (pin "2") (pinfunction "1_2") (pintype "passive"))
      (node (ref "RN1") (pin "7") (pinfunction "2_7") (pintype "passive"))
      (node (ref "RN1") (pin "8") (pinfunction "2_8") (pintype "passive"))
      (node (ref "RN2") (pin "1") (pinfunction "1_1") (pintype "passive"))
      (node (ref "RN2") (pin "4") (pinfunction "1_4") (pintype "passive"))
      (node (ref "RN2") (pin "5") (pinfunction "2_5") (pintype "passive"))
      (node (ref "RN2") (pin "8") (pinfunction "2_8") (pintype "passive"))
      (node (ref "RN4") (pin "1") (pinfunction "1_1") (pintype "passive"))
      (node (ref "RN4") (pin "2") (pinfunction "1_2") (pintype "passive"))
      (node (ref "RN4") (pin "5") (pinfunction "2_5") (pintype "passive"))
      (node (ref "RN4") (pin "7") (pinfunction "2_7") (pintype "passive"))
      (node (ref "SPI") (pin "6") (pinfunction "6_6") (pintype "passive"))
      (node (ref "T2") (pin "3") (pinfunction "G_3") (pintype "passive"))
      (node (ref "U1") (pin "106") (pinfunction "GND3_106") (pintype "power_in"))
      (node (ref "U1") (pin "12") (pinfunction "GND1_12") (pintype "power_in"))
      (node (ref "U1") (pin "126") (pinfunction "GND4_126") (pintype "power_in"))
      (node (ref "U1") (pin "33") (pinfunction "GNDPLL_33") (pintype "power_in"))
      (node (ref "U1") (pin "44") (pinfunction "GNDUTMI_44") (pintype "power_in"))
      (node (ref "U1") (pin "46") (pinfunction "JTAGSEL_46") (pintype "passive"))
      (node (ref "U1") (pin "54") (pinfunction "GNDBU_54") (pintype "power_in"))
      (node (ref "U1") (pin "58") (pinfunction "GND2_58") (pintype "power_in"))
      (node (ref "U1") (pin "74") (pinfunction "GNDANA_74") (pintype "power_in"))
      (node (ref "USB1") (pin "5") (pinfunction "UGND_5") (pintype "power_in"))
      (node (ref "USB1") (pin "P$1") (pinfunction "G1_P$1") (pintype "passive"))
      (node (ref "USB1") (pin "P$10") (pinfunction "G10_P$10") (pintype "passive"))
      (node (ref "USB1") (pin "P$11") (pinfunction "G11_P$11") (pintype "passive"))
      (node (ref "USB1") (pin "P$2") (pinfunction "G2_P$2") (pintype "passive"))
      (node (ref "USB1") (pin "P$3") (pinfunction "G3_P$3") (pintype "passive"))
      (node (ref "USB1") (pin "P$4") (pinfunction "G4_P$4") (pintype "passive"))
      (node (ref "USB1") (pin "P$5") (pinfunction "G5_P$5") (pintype "passive"))
      (node (ref "USB1") (pin "P$6") (pinfunction "G6_P$6") (pintype "passive"))
      (node (ref "USB1") (pin "P$7") (pinfunction "G7_P$7") (pintype "passive"))
      (node (ref "USB1") (pin "P$8") (pinfunction "G8_P$8") (pintype "passive"))
      (node (ref "USB1") (pin "P$9") (pinfunction "G9_P$9") (pintype "passive"))
      (node (ref "USB1") (pin "S1") (pinfunction "SH1_S1") (pintype "passive"))
      (node (ref "USB1") (pin "S2") (pinfunction "SH2_S2") (pintype "passive"))
      (node (ref "USB1") (pin "S3") (pinfunction "SH3_S3") (pintype "passive"))
      (node (ref "USB1") (pin "S4") (pinfunction "SH4_S4") (pintype "passive"))
      (node (ref "X2") (pin "1") (pinfunction "1_1") (pintype "power_in"))
      (node (ref "X2") (pin "3") (pinfunction "3_3") (pintype "power_in"))
      (node (ref "XIO") (pin "35") (pinfunction "35_35") (pintype "passive"))
      (node (ref "XIO") (pin "36") (pinfunction "36_36") (pintype "passive"))
      (node (ref "Y1") (pin "2") (pinfunction "GND_2") (pintype "passive"))
      (node (ref "Y1") (pin "4") (pinfunction "GND_4") (pintype "passive"))
      (node (ref "Y4") (pin "2") (pinfunction "GND_2") (pintype "passive"))
      (node (ref "Y4") (pin "4") (pinfunction "GND_4") (pintype "passive"))
      (node (ref "Z1") (pin "2") (pinfunction "2_2") (pintype "passive"))
      (node (ref "Z2") (pin "2") (pinfunction "2_2") (pintype "passive"))
      (node (ref "Z3") (pin "1") (pinfunction "1_1") (pintype "passive"))
      (node (ref "Z4") (pin "1") (pinfunction "1_1") (pintype "passive"))
      (node (ref "Z5") (pin "1") (pinfunction "1_1") (pintype "passive"))
    )
    (net (code "163") (name "Net-(D5-A)") (class "Default")
      (node (ref "D5") (pin "P$2") (pinfunction "A_P$2") (pintype "passive"))
      (node (ref "L6") (pin "1") (pinfunction "1_1") (pintype "passive"))
    )
    (net (code "164") (name "Net-(Q2-B)") (class "Default")
      (node (ref "Q2") (pin "1") (pinfunction "B_1") (pintype "passive"))
      (node (ref "R3") (pin "2") (pinfunction "2_2") (pintype "passive"))
      (node (ref "RN4") (pin "8") (pinfunction "2_8") (pintype "passive"))
    )
    (net (code "165") (name "Net-(R14-Pad2)") (class "Default")
      (node (ref "R14") (pin "2") (pinfunction "2_2") (pintype "passive"))
      (node (ref "TX1") (pin "A") (pinfunction "A_A") (pintype "passive"))
    )
    (net (code "166") (name "Net-(R15-Pad2)") (class "Default")
      (node (ref "R15") (pin "2") (pinfunction "2_2") (pintype "passive"))
      (node (ref "RX1") (pin "A") (pinfunction "A_A") (pintype "passive"))
    )
    (net (code "167") (name "Net-(RN3-Pad1)") (class "Default")
      (node (ref "RN3") (pin "1") (pinfunction "1_1") (pintype "passive"))
      (node (ref "RX") (pin "A") (pinfunction "A_A") (pintype "passive"))
    )
    (net (code "168") (name "Net-(RN3B-1)") (class "Default")
      (node (ref "RN3") (pin "2") (pinfunction "1_2") (pintype "passive"))
      (node (ref "TX") (pin "A") (pinfunction "A_A") (pintype "passive"))
    )
    (net (code "169") (name "Net-(RN3C-1)") (class "Default")
      (node (ref "L") (pin "A") (pinfunction "A_A") (pintype "passive"))
      (node (ref "RN3") (pin "3") (pinfunction "1_3") (pintype "passive"))
    )
    (net (code "170") (name "Net-(RN3D-1)") (class "Default")
      (node (ref "ON") (pin "A") (pinfunction "A_A") (pintype "passive"))
      (node (ref "RN3") (pin "4") (pinfunction "1_4") (pintype "passive"))
    )
    (net (code "171") (name "Net-(U1-DFSDM)") (class "Default")
      (node (ref "R5") (pin "2") (pinfunction "2_2") (pintype "passive"))
      (node (ref "U1") (pin "43") (pinfunction "DFSDM_43") (pintype "passive"))
    )
    (net (code "172") (name "Net-(U1-DFSDP)") (class "Default")
      (node (ref "R6") (pin "2") (pinfunction "2_2") (pintype "passive"))
      (node (ref "U1") (pin "42") (pinfunction "DFSDP_42") (pintype "passive"))
    )
    (net (code "173") (name "Net-(U1-FWUP)") (class "Default")
      (node (ref "R4") (pin "1") (pinfunction "1_1") (pintype "passive"))
      (node (ref "U1") (pin "53") (pinfunction "FWUP_53") (pintype "passive"))
    )
    (net (code "174") (name "Net-(U1-TST)") (class "Default")
      (node (ref "R8") (pin "2") (pinfunction "2_2") (pintype "passive"))
      (node (ref "U1") (pin "51") (pinfunction "TST_51") (pintype "passive"))
    )
    (net (code "175") (name "unconnected-(IC6-(AIN0{slash}INT1)PD1-Pad7)") (class "Default")
      (node (ref "IC6") (pin "7") (pinfunction "(AIN0/INT1)PD1_7") (pintype "passive"))
    )
    (net (code "176") (name "unconnected-(IC6-(AIN2{slash}PCINT11)PC2-Pad5)") (class "Default")
      (node (ref "IC6") (pin "5") (pinfunction "(AIN2/PCINT11)PC2_5") (pintype "passive"))
    )
    (net (code "177") (name "unconnected-(IC6-(OC0B{slash}INT0)PD0-Pad6)") (class "Default")
      (node (ref "IC6") (pin "6") (pinfunction "(OC0B/INT0)PD0_6") (pintype "passive"))
    )
    (net (code "178") (name "unconnected-(IC6-(PCINT9{slash}OC1B)PC5-Pad25)") (class "Default")
      (node (ref "IC6") (pin "25") (pinfunction "(PCINT9/OC1B)PC5_25") (pintype "passive"))
    )
    (net (code "179") (name "unconnected-(IC6-(RTS{slash}AIN5{slash}INT6)PD6-Pad12)") (class "Default")
      (node (ref "IC6") (pin "12") (pinfunction "(RTS/AIN5/INT6)PD6_12") (pintype "passive"))
    )
    (net (code "180") (name "unconnected-(IC6-(SS{slash}PCINT0)PB0-Pad14)") (class "Default")
      (node (ref "IC6") (pin "14") (pinfunction "(SS/PCINT0)PB0_14") (pintype "passive"))
    )
    (net (code "181") (name "unconnected-(J3-ID-PadP4)") (class "Default")
      (node (ref "J3") (pin "P4") (pinfunction "ID_P4") (pintype "passive"))
    )
    (net (code "182") (name "unconnected-(JTAG-Pad7)") (class "Default")
      (node (ref "JTAG") (pin "7") (pinfunction "7_7") (pintype "passive"))
    )
    (net (code "183") (name "unconnected-(POWER-Pad1)") (class "Default")
      (node (ref "POWER") (pin "1") (pinfunction "1_1") (pintype "passive"))
    )
    (net (code "184") (name "unconnected-(RESET-5-GND-Pad5)") (class "Default")
      (node (ref "RESET") (pin "5") (pinfunction "5-GND_5") (pintype "power_in"))
    )
    (net (code "185") (name "unconnected-(RN5C-1-Pad3)") (class "Default")
      (node (ref "RN5") (pin "3") (pinfunction "1_3") (pintype "passive"))
    )
    (net (code "186") (name "unconnected-(RN5C-2-Pad6)") (class "Default")
      (node (ref "RN5") (pin "6") (pinfunction "2_6") (pintype "passive"))
    )
    (net (code "187") (name "unconnected-(RN5D-1-Pad4)") (class "Default")
      (node (ref "RN5") (pin "4") (pinfunction "1_4") (pintype "passive"))
    )
    (net (code "188") (name "unconnected-(RN5D-2-Pad5)") (class "Default")
      (node (ref "RN5") (pin "5") (pinfunction "2_5") (pintype "passive"))
    )
    (net (code "189") (name "unconnected-(U1-NRST-Pad69)") (class "Default")
      (node (ref "U1") (pin "69") (pinfunction "NRST_69") (pintype "passive"))
    )
    (net (code "190") (name "unconnected-(U1-PB22-Pad141)") (class "Default")
      (node (ref "U1") (pin "141") (pinfunction "PB22_141") (pintype "passive"))
    )
    (net (code "191") (name "unconnected-(U1-PB24-Pad143)") (class "Default")
      (node (ref "U1") (pin "143") (pinfunction "PB24_143") (pintype "passive"))
    )
    (net (code "192") (name "unconnected-(U1-PC10-Pad117)") (class "Default")
      (node (ref "U1") (pin "117") (pinfunction "PC10_117") (pintype "passive"))
    )
    (net (code "193") (name "unconnected-(U1-PC11-Pad93)") (class "Default")
      (node (ref "U1") (pin "93") (pinfunction "PC11_93") (pintype "passive"))
    )
    (net (code "194") (name "unconnected-(U1-PC20-Pad131)") (class "Default")
      (node (ref "U1") (pin "131") (pinfunction "PC20_131") (pintype "passive"))
    )
    (net (code "195") (name "unconnected-(U1-PC27-Pad138)") (class "Default")
      (node (ref "U1") (pin "138") (pinfunction "PC27_138") (pintype "passive"))
    )
    (net (code "196") (name "unconnected-(U1-SHDN-Pad50)") (class "Default")
      (node (ref "U1") (pin "50") (pinfunction "SHDN_50") (pintype "output"))
    )
  )
)
